# LinTempCont_4ch_proto.net
KiCad netlist of a schematic drawn in EAGLE
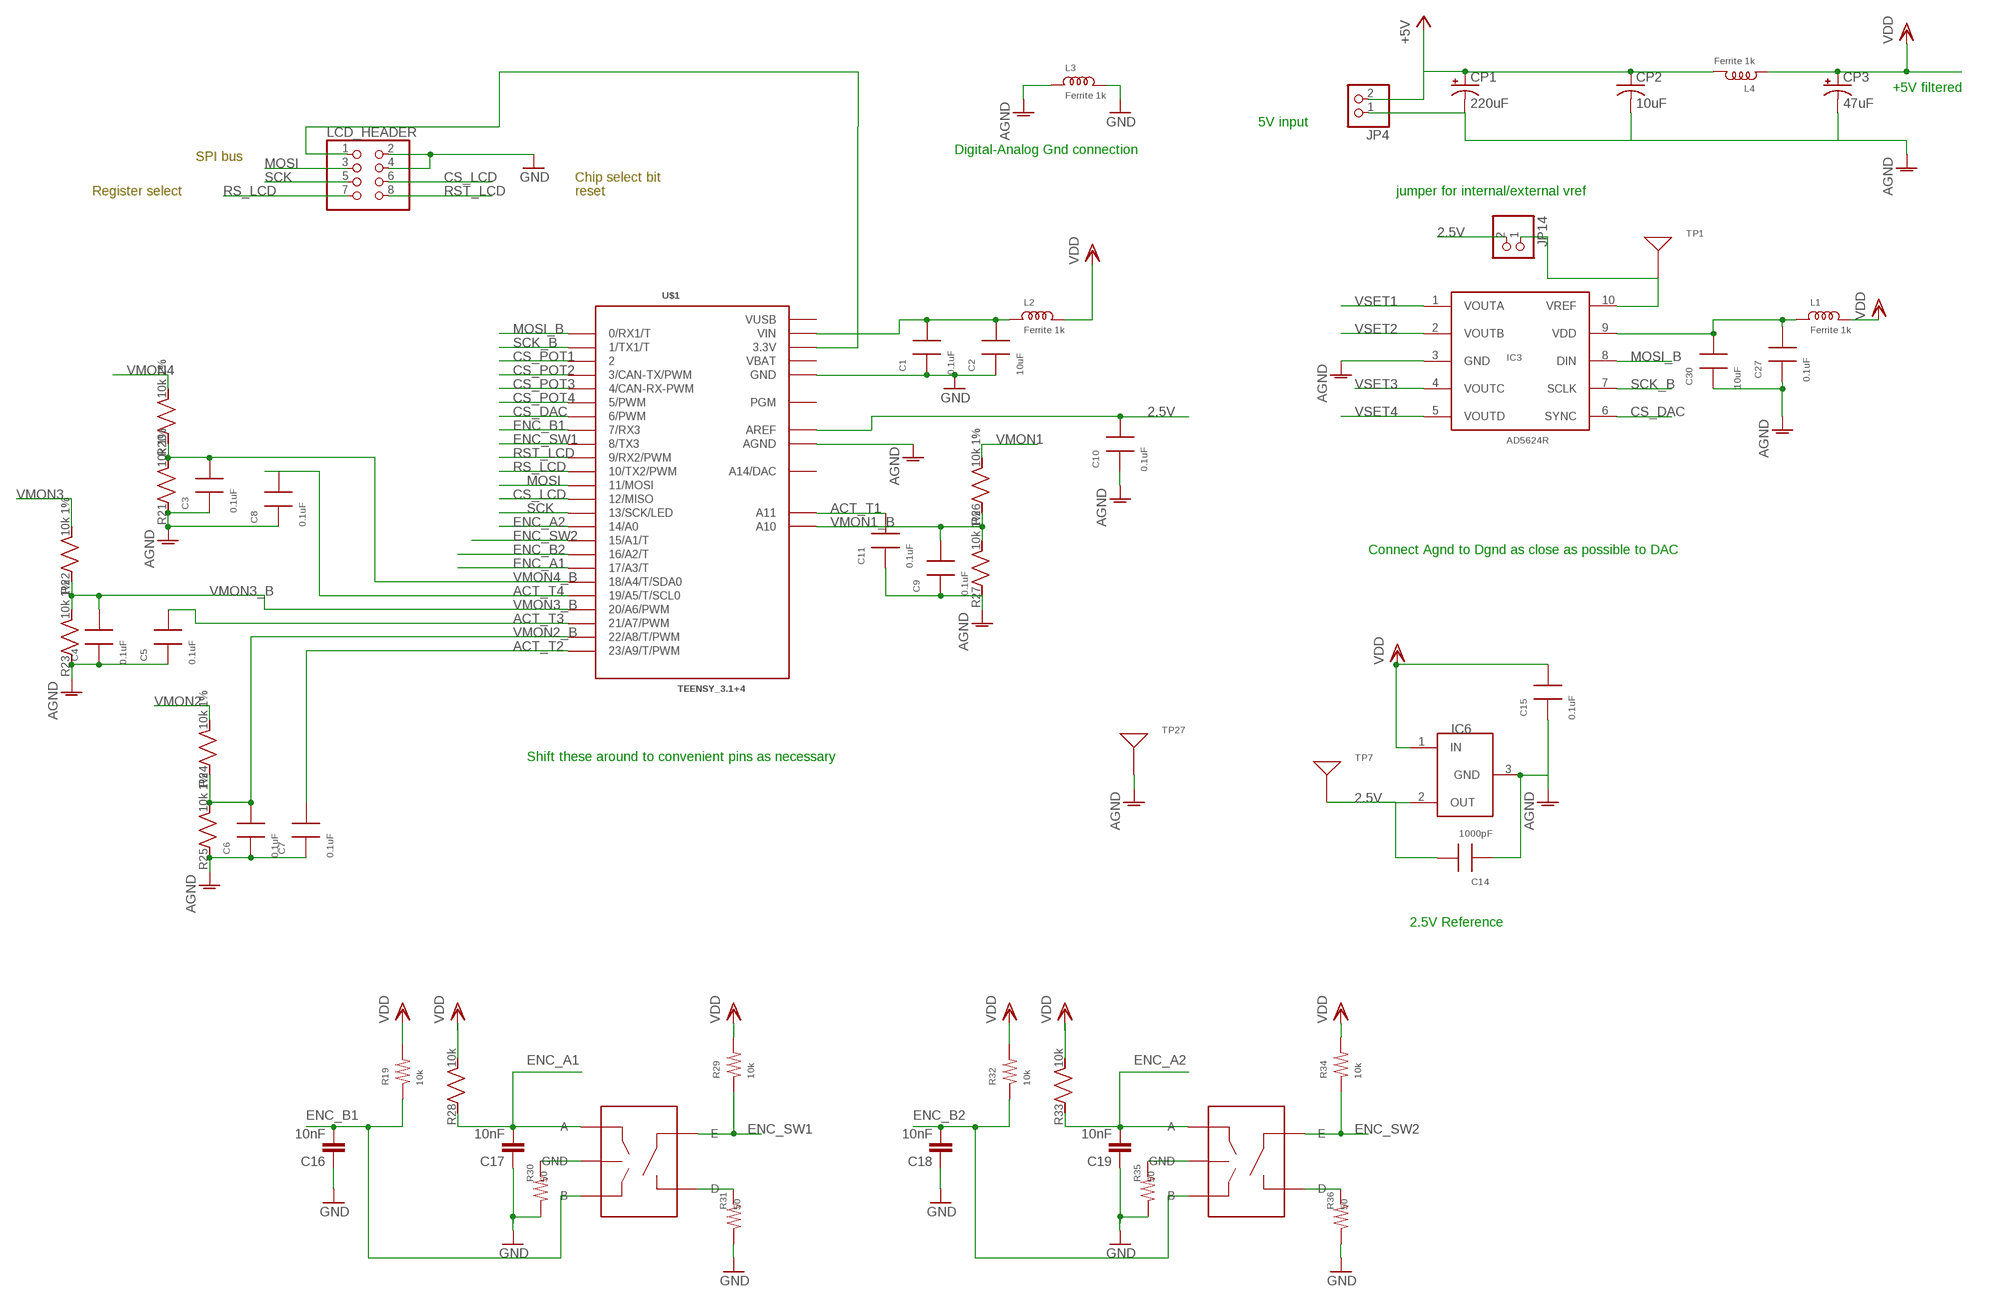
[diagram p0: schematic, sheet 1]
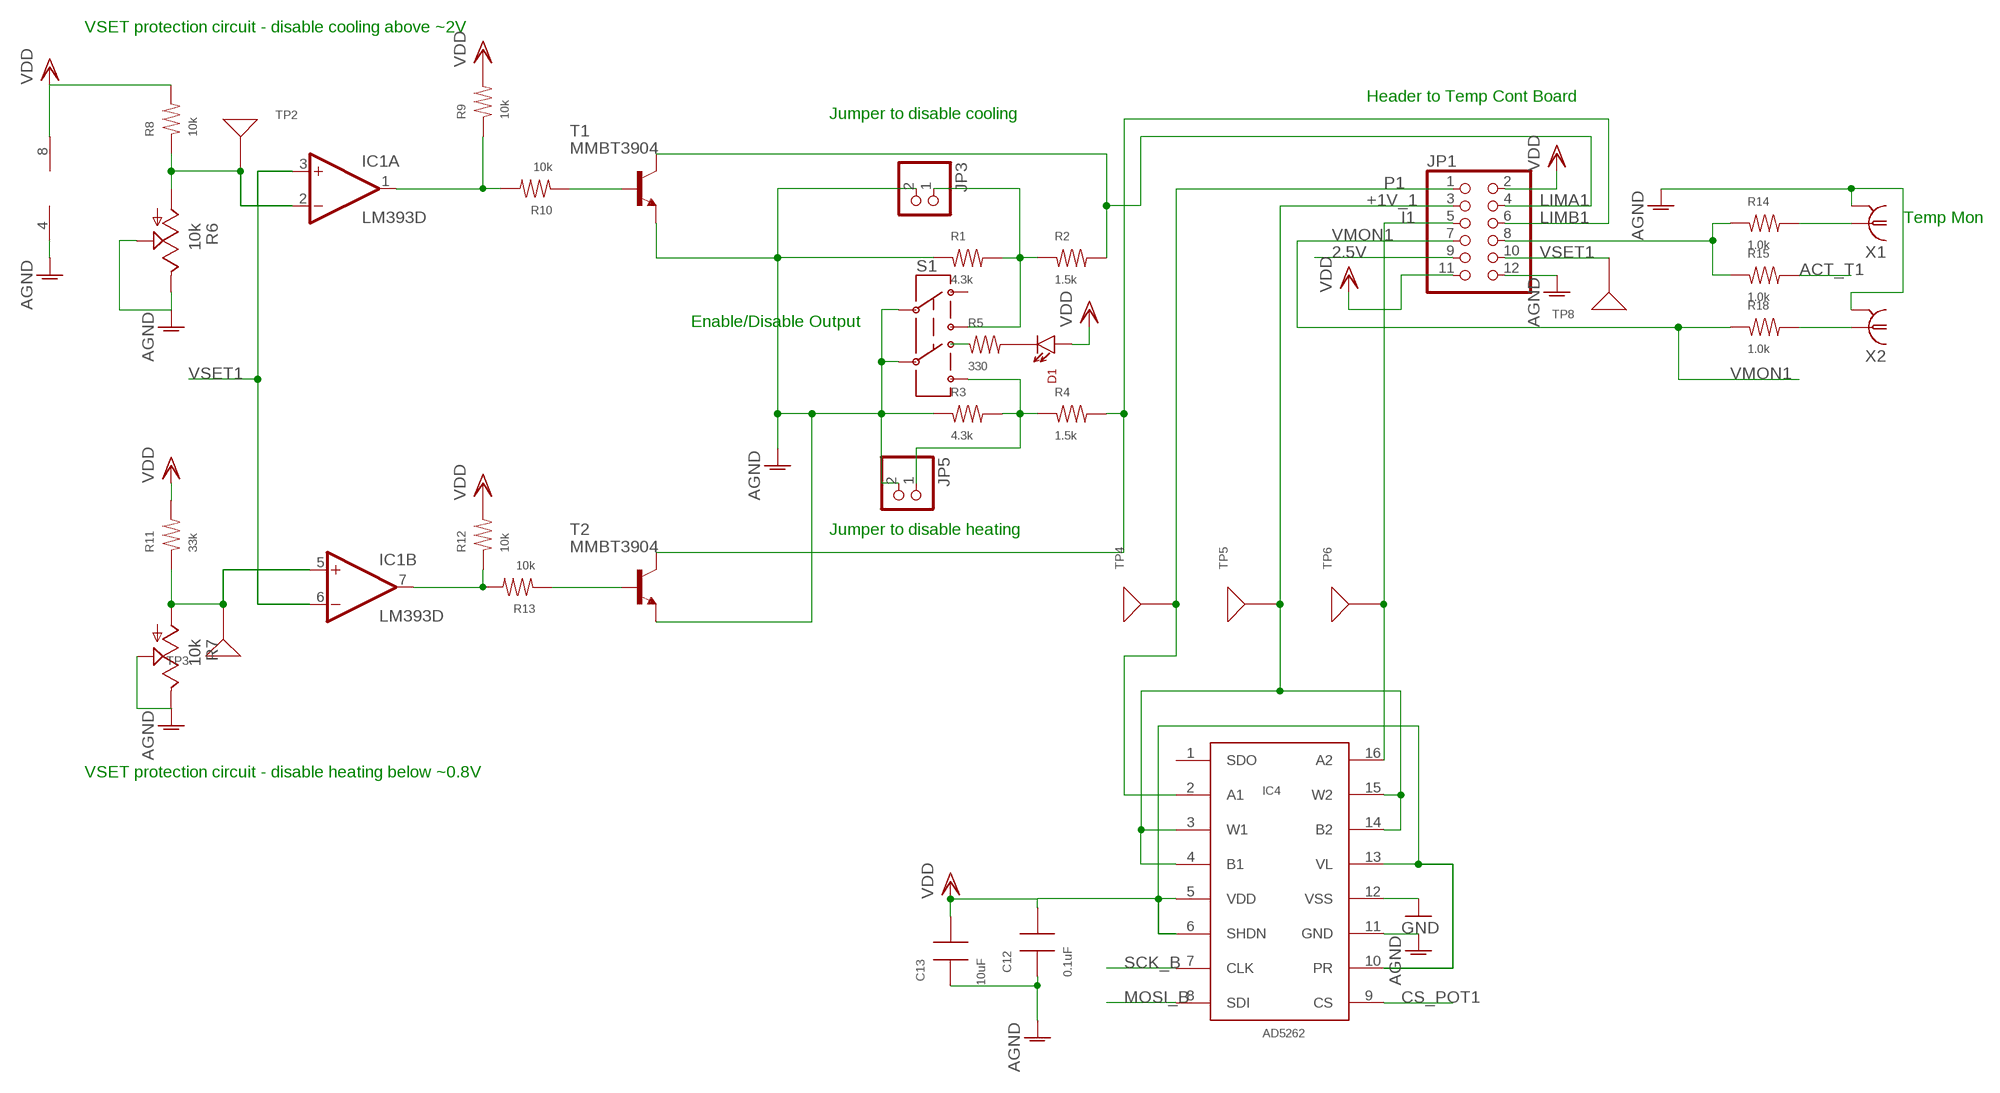
[diagram p1: schematic, sheet 2]
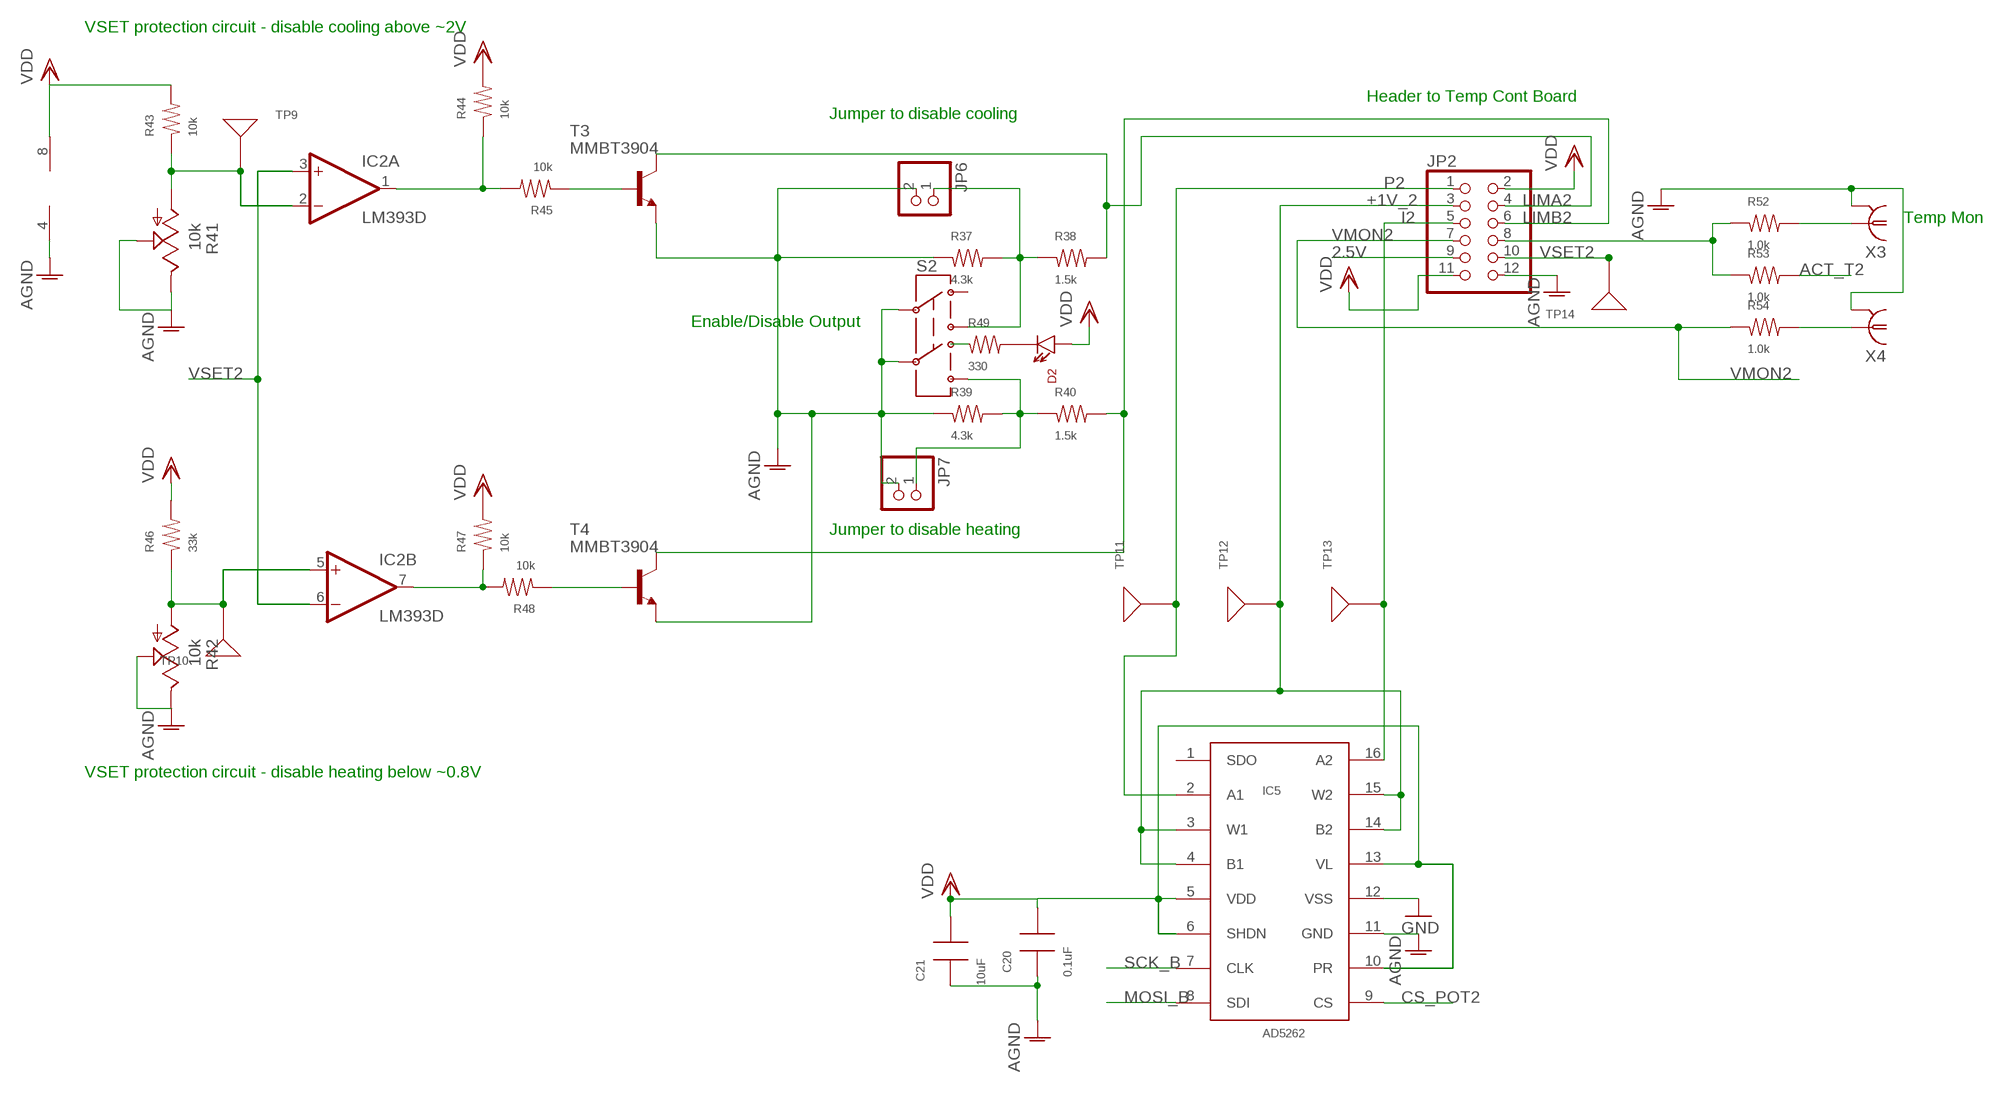
[diagram p2: schematic, sheet 3]
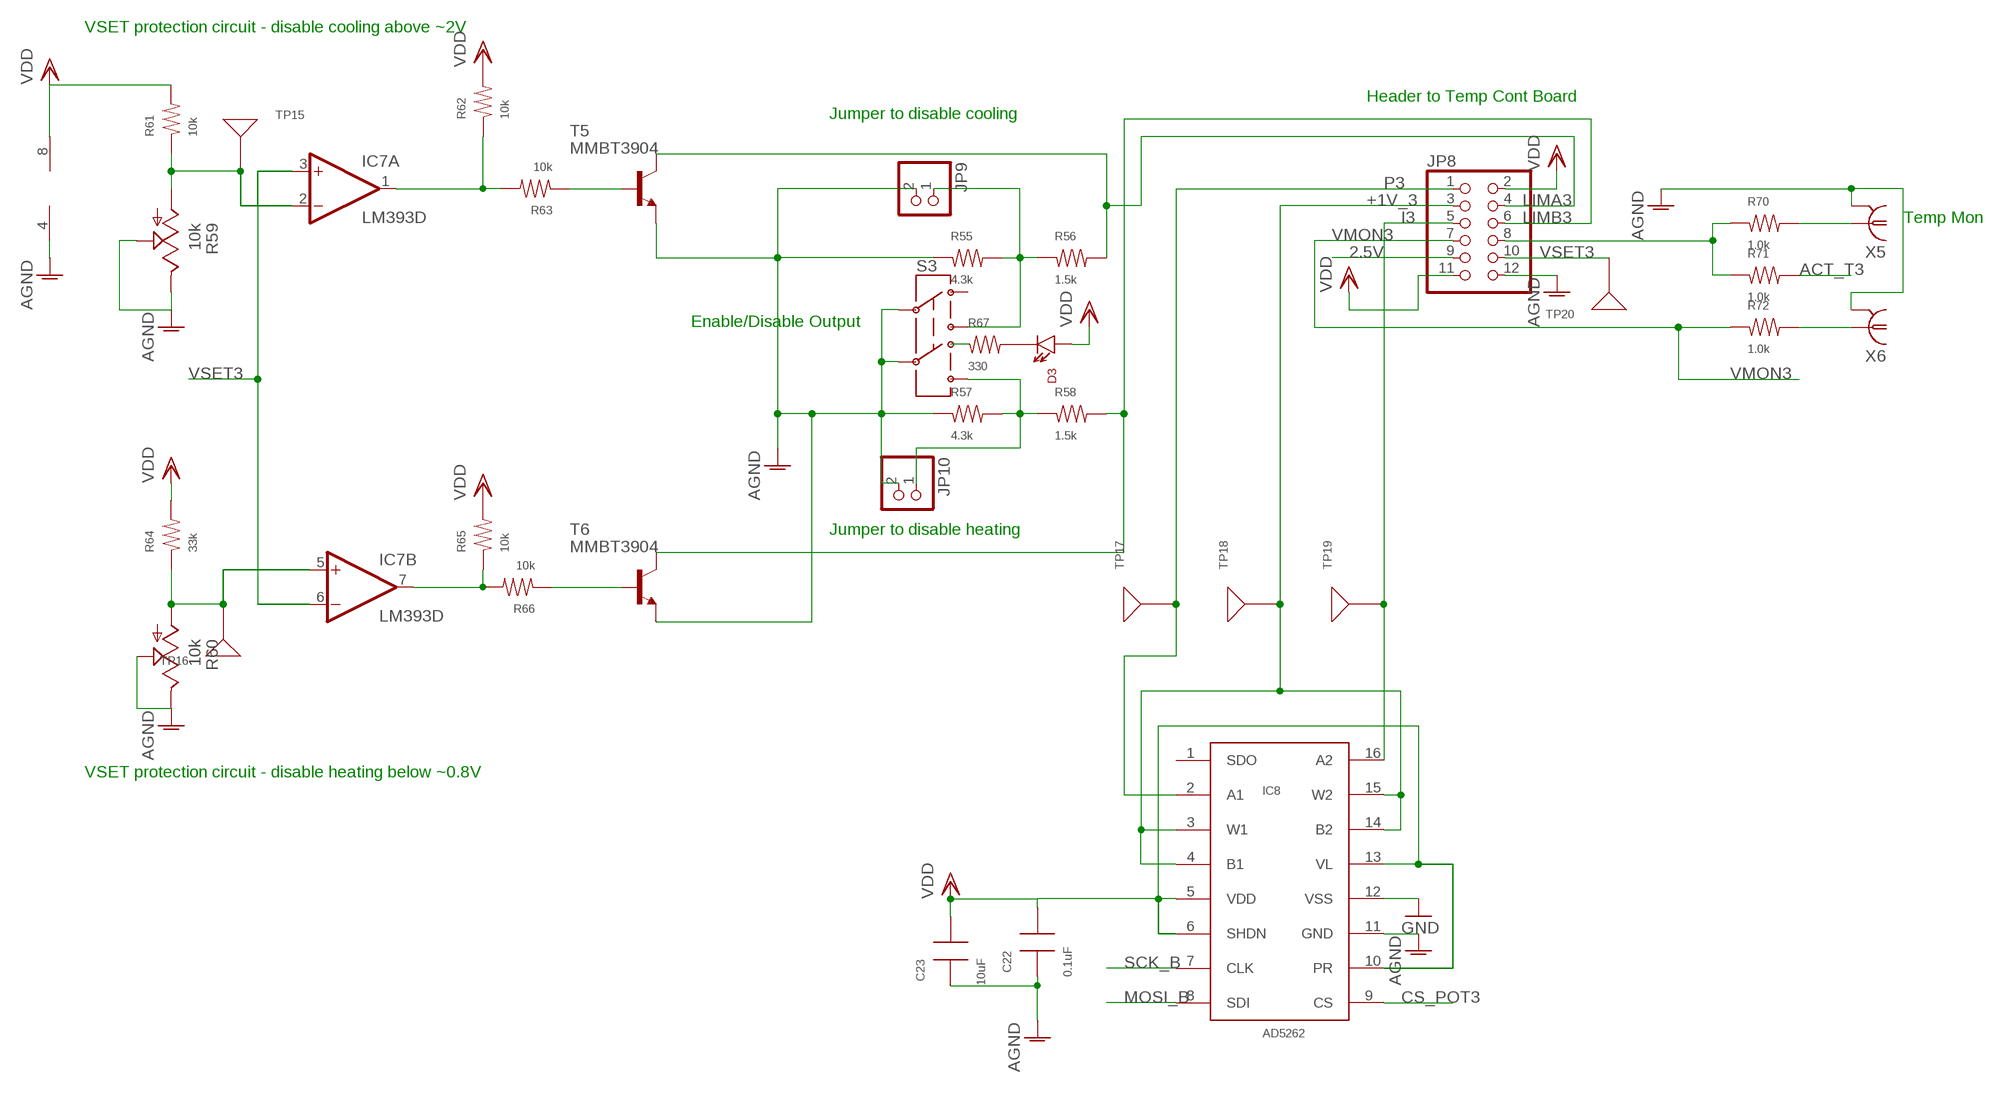
[diagram p3: schematic, sheet 4]
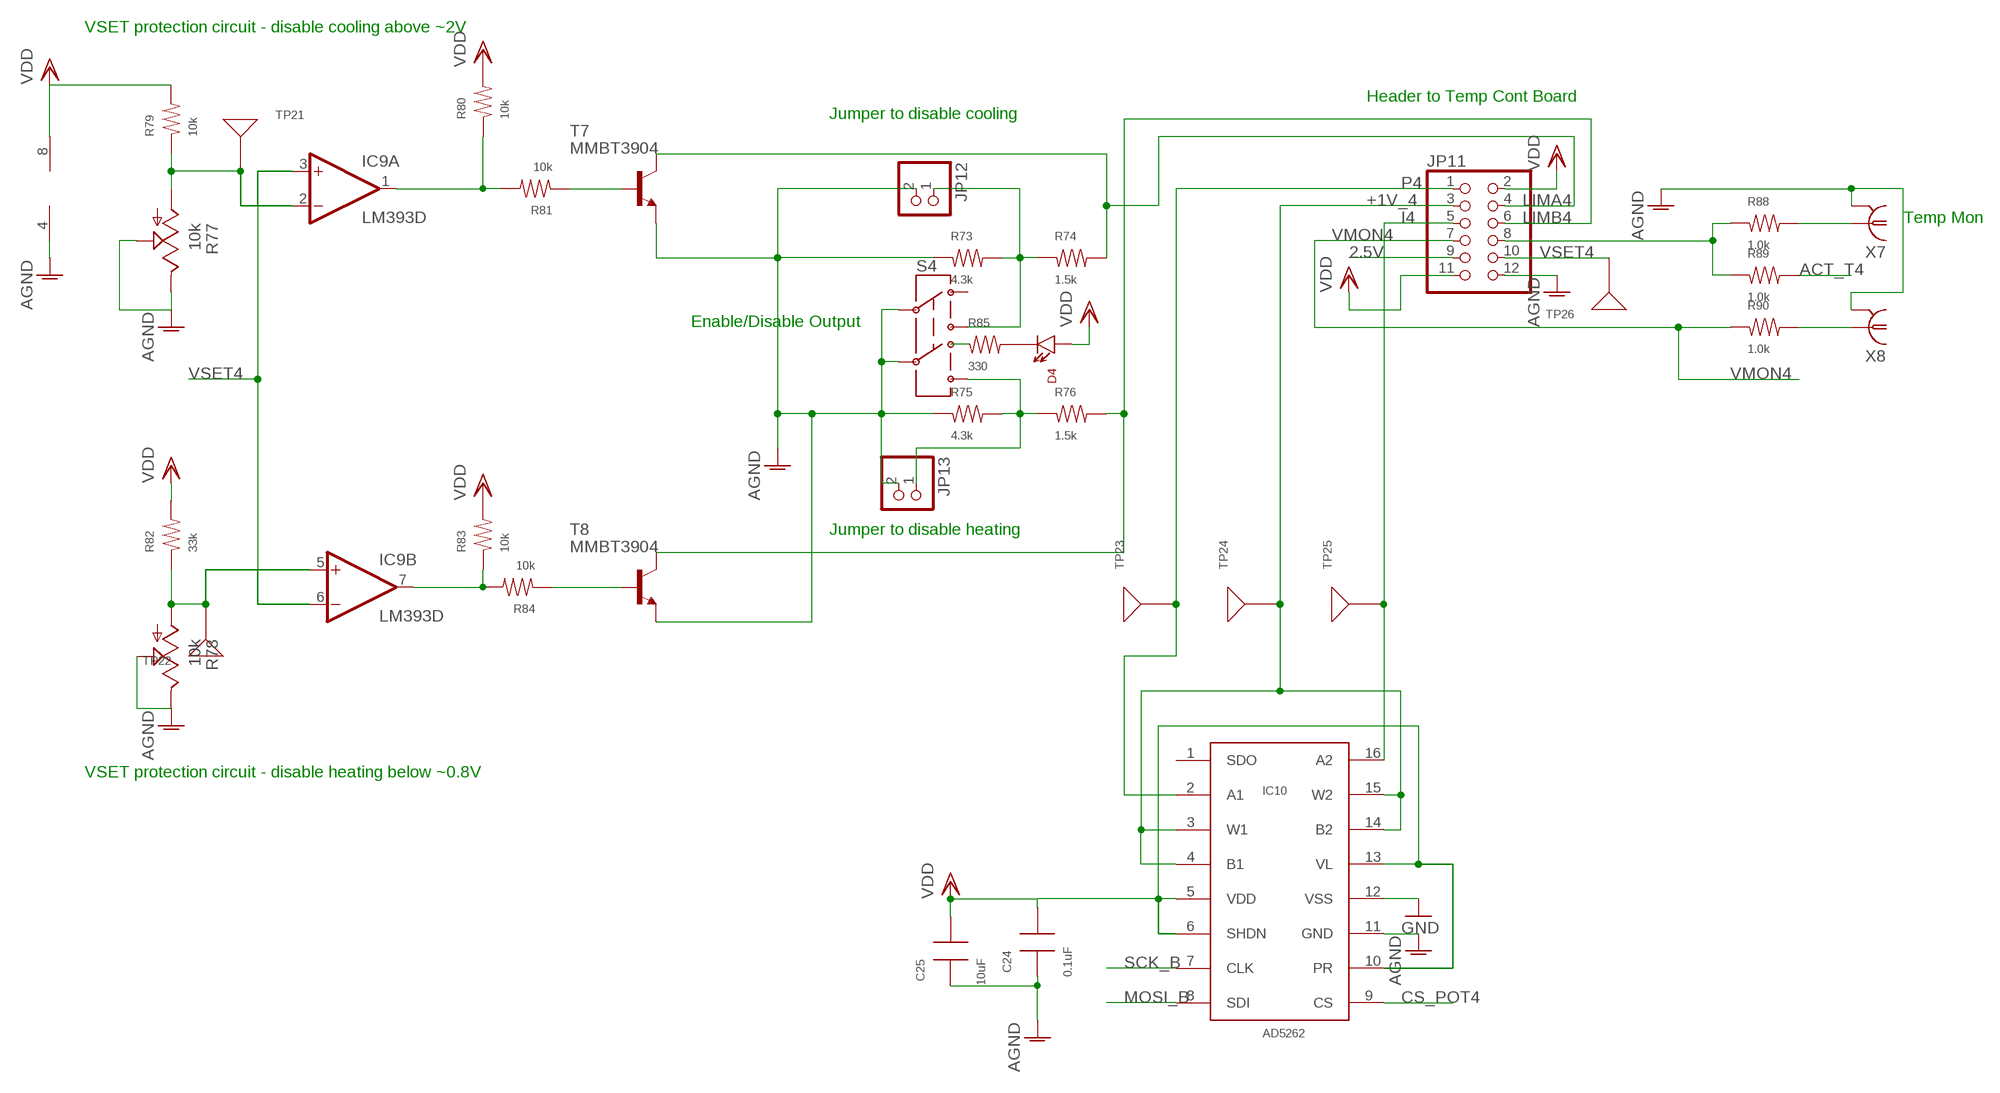
[diagram p4: schematic, sheet 5]

(export (version "E")
  (design (tool "Eeschema 10.0.6"))
  (components
    (comp (ref "C22")
      (value "0.1uF")
      (footprint "eagle-import:0603")
      (libsource (lib "eagle-import") (part "CAP0603"))
    )
    (comp (ref "C23")
      (value "10uF")
      (footprint "eagle-import:0805")
      (libsource (lib "eagle-import") (part "CAP0805"))
    )
    (comp (ref "D3")
      (value "LED/MINI-IND")
      (footprint "eagle-import:HLMP--F0010")
      (libsource (lib "eagle-import") (part "LED/MINI-IND"))
    )
    (comp (ref "IC7")
      (value "LM393D")
      (footprint "eagle-import:SO08")
      (libsource (lib "eagle-import") (part "LM393D"))
    )
    (comp (ref "IC8")
      (value "AD5262")
      (footprint "eagle-import:TSSOP16")
      (libsource (lib "eagle-import") (part "AD5262"))
    )
    (comp (ref "JP8")
      (value "PINHD-2X6/90")
      (footprint "eagle-import:2X06_90")
      (libsource (lib "eagle-import") (part "PINHD-2X6/90"))
    )
    (comp (ref "JP9")
      (value "PINHD-1X2")
      (footprint "eagle-import:1X02")
      (libsource (lib "eagle-import") (part "PINHD-1X2"))
    )
    (comp (ref "JP10")
      (value "PINHD-1X2")
      (footprint "eagle-import:1X02")
      (libsource (lib "eagle-import") (part "PINHD-1X2"))
    )
    (comp (ref "R55")
      (value "4.3k")
      (footprint "eagle-import:0603")
      (libsource (lib "eagle-import") (part "RES0603"))
    )
    (comp (ref "R56")
      (value "1.5k")
      (footprint "eagle-import:0603")
      (libsource (lib "eagle-import") (part "RES0603"))
    )
    (comp (ref "R57")
      (value "4.3k")
      (footprint "eagle-import:0603")
      (libsource (lib "eagle-import") (part "RES0603"))
    )
    (comp (ref "R58")
      (value "1.5k")
      (footprint "eagle-import:0603")
      (libsource (lib "eagle-import") (part "RES0603"))
    )
    (comp (ref "R59")
      (value "10k")
      (footprint "eagle-import:64WPOT")
      (libsource (lib "eagle-import") (part "MODEL64_TRIMPOT/TOP-ADJ"))
    )
    (comp (ref "R60")
      (value "10k")
      (footprint "eagle-import:64WPOT")
      (libsource (lib "eagle-import") (part "MODEL64_TRIMPOT/TOP-ADJ"))
    )
    (comp (ref "R61")
      (value "10k")
      (footprint "eagle-import:0603")
      (libsource (lib "eagle-import") (part "RES0603"))
    )
    (comp (ref "R62")
      (value "10k")
      (footprint "eagle-import:0603")
      (libsource (lib "eagle-import") (part "RES0603"))
    )
    (comp (ref "R63")
      (value "10k")
      (footprint "eagle-import:0603")
      (libsource (lib "eagle-import") (part "RES0603"))
    )
    (comp (ref "R64")
      (value "33k")
      (footprint "eagle-import:0603")
      (libsource (lib "eagle-import") (part "RES0603"))
    )
    (comp (ref "R65")
      (value "10k")
      (footprint "eagle-import:0603")
      (libsource (lib "eagle-import") (part "RES0603"))
    )
    (comp (ref "R66")
      (value "10k")
      (footprint "eagle-import:0603")
      (libsource (lib "eagle-import") (part "RES0603"))
    )
    (comp (ref "R67")
      (value "330")
      (footprint "eagle-import:0603")
      (libsource (lib "eagle-import") (part "RES0603"))
    )
    (comp (ref "R70")
      (value "1.0k")
      (footprint "eagle-import:0603")
      (libsource (lib "eagle-import") (part "RES0603"))
    )
    (comp (ref "R71")
      (value "1.0k")
      (footprint "eagle-import:0603")
      (libsource (lib "eagle-import") (part "RES0603"))
    )
    (comp (ref "R72")
      (value "1.0k")
      (footprint "eagle-import:0603")
      (libsource (lib "eagle-import") (part "RES0603"))
    )
    (comp (ref "S3")
      (value "SWITCH-DPDT/VER")
      (footprint "eagle-import:E-SWITCH-100-M7")
      (libsource (lib "eagle-import") (part "SWITCH-DPDT/VER"))
    )
    (comp (ref "T5")
      (value "MMBT3904")
      (footprint "eagle-import:SOT-23")
      (libsource (lib "eagle-import") (part "MMBT3904"))
    )
    (comp (ref "T6")
      (value "MMBT3904")
      (footprint "eagle-import:SOT-23")
      (libsource (lib "eagle-import") (part "MMBT3904"))
    )
    (comp (ref "TP15")
      (value "TESTPT")
      (footprint "eagle-import:1206TESTPAD")
      (libsource (lib "eagle-import") (part "TESTPT"))
    )
    (comp (ref "TP16")
      (value "TESTPT")
      (footprint "eagle-import:1206TESTPAD")
      (libsource (lib "eagle-import") (part "TESTPT"))
    )
    (comp (ref "TP17")
      (value "TESTPT")
      (footprint "eagle-import:1206TESTPAD")
      (libsource (lib "eagle-import") (part "TESTPT"))
    )
    (comp (ref "TP18")
      (value "TESTPT")
      (footprint "eagle-import:1206TESTPAD")
      (libsource (lib "eagle-import") (part "TESTPT"))
    )
    (comp (ref "TP19")
      (value "TESTPT")
      (footprint "eagle-import:1206TESTPAD")
      (libsource (lib "eagle-import") (part "TESTPT"))
    )
    (comp (ref "TP20")
      (value "TESTPT")
      (footprint "eagle-import:1206TESTPAD")
      (libsource (lib "eagle-import") (part "TESTPT"))
    )
    (comp (ref "X5")
      (value "BNC-H")
      (footprint "eagle-import:BNC90")
      (libsource (lib "eagle-import") (part "BNC-H"))
    )
    (comp (ref "X6")
      (value "BNC-H")
      (footprint "eagle-import:BNC90")
      (libsource (lib "eagle-import") (part "BNC-H"))
    )
    (comp (ref "C24")
      (value "0.1uF")
      (footprint "eagle-import:0603")
      (libsource (lib "eagle-import") (part "CAP0603"))
    )
    (comp (ref "C25")
      (value "10uF")
      (footprint "eagle-import:0805")
      (libsource (lib "eagle-import") (part "CAP0805"))
    )
    (comp (ref "D4")
      (value "LED/MINI-IND")
      (footprint "eagle-import:HLMP--F0010")
      (libsource (lib "eagle-import") (part "LED/MINI-IND"))
    )
    (comp (ref "IC9")
      (value "LM393D")
      (footprint "eagle-import:SO08")
      (libsource (lib "eagle-import") (part "LM393D"))
    )
    (comp (ref "IC10")
      (value "AD5262")
      (footprint "eagle-import:TSSOP16")
      (libsource (lib "eagle-import") (part "AD5262"))
    )
    (comp (ref "JP11")
      (value "PINHD-2X6/90")
      (footprint "eagle-import:2X06_90")
      (libsource (lib "eagle-import") (part "PINHD-2X6/90"))
    )
    (comp (ref "JP12")
      (value "PINHD-1X2")
      (footprint "eagle-import:1X02")
      (libsource (lib "eagle-import") (part "PINHD-1X2"))
    )
    (comp (ref "JP13")
      (value "PINHD-1X2")
      (footprint "eagle-import:1X02")
      (libsource (lib "eagle-import") (part "PINHD-1X2"))
    )
    (comp (ref "R73")
      (value "4.3k")
      (footprint "eagle-import:0603")
      (libsource (lib "eagle-import") (part "RES0603"))
    )
    (comp (ref "R74")
      (value "1.5k")
      (footprint "eagle-import:0603")
      (libsource (lib "eagle-import") (part "RES0603"))
    )
    (comp (ref "R75")
      (value "4.3k")
      (footprint "eagle-import:0603")
      (libsource (lib "eagle-import") (part "RES0603"))
    )
    (comp (ref "R76")
      (value "1.5k")
      (footprint "eagle-import:0603")
      (libsource (lib "eagle-import") (part "RES0603"))
    )
    (comp (ref "R77")
      (value "10k")
      (footprint "eagle-import:64WPOT")
      (libsource (lib "eagle-import") (part "MODEL64_TRIMPOT/TOP-ADJ"))
    )
    (comp (ref "R78")
      (value "10k")
      (footprint "eagle-import:64WPOT")
      (libsource (lib "eagle-import") (part "MODEL64_TRIMPOT/TOP-ADJ"))
    )
    (comp (ref "R79")
      (value "10k")
      (footprint "eagle-import:0603")
      (libsource (lib "eagle-import") (part "RES0603"))
    )
    (comp (ref "R80")
      (value "10k")
      (footprint "eagle-import:0603")
      (libsource (lib "eagle-import") (part "RES0603"))
    )
    (comp (ref "R81")
      (value "10k")
      (footprint "eagle-import:0603")
      (libsource (lib "eagle-import") (part "RES0603"))
    )
    (comp (ref "R82")
      (value "33k")
      (footprint "eagle-import:0603")
      (libsource (lib "eagle-import") (part "RES0603"))
    )
    (comp (ref "R83")
      (value "10k")
      (footprint "eagle-import:0603")
      (libsource (lib "eagle-import") (part "RES0603"))
    )
    (comp (ref "R84")
      (value "10k")
      (footprint "eagle-import:0603")
      (libsource (lib "eagle-import") (part "RES0603"))
    )
    (comp (ref "R85")
      (value "330")
      (footprint "eagle-import:0603")
      (libsource (lib "eagle-import") (part "RES0603"))
    )
    (comp (ref "R88")
      (value "1.0k")
      (footprint "eagle-import:0603")
      (libsource (lib "eagle-import") (part "RES0603"))
    )
    (comp (ref "R89")
      (value "1.0k")
      (footprint "eagle-import:0603")
      (libsource (lib "eagle-import") (part "RES0603"))
    )
    (comp (ref "R90")
      (value "1.0k")
      (footprint "eagle-import:0603")
      (libsource (lib "eagle-import") (part "RES0603"))
    )
    (comp (ref "S4")
      (value "SWITCH-DPDT/VER")
      (footprint "eagle-import:E-SWITCH-100-M7")
      (libsource (lib "eagle-import") (part "SWITCH-DPDT/VER"))
    )
    (comp (ref "T7")
      (value "MMBT3904")
      (footprint "eagle-import:SOT-23")
      (libsource (lib "eagle-import") (part "MMBT3904"))
    )
    (comp (ref "T8")
      (value "MMBT3904")
      (footprint "eagle-import:SOT-23")
      (libsource (lib "eagle-import") (part "MMBT3904"))
    )
    (comp (ref "TP21")
      (value "TESTPT")
      (footprint "eagle-import:1206TESTPAD")
      (libsource (lib "eagle-import") (part "TESTPT"))
    )
    (comp (ref "TP22")
      (value "TESTPT")
      (footprint "eagle-import:1206TESTPAD")
      (libsource (lib "eagle-import") (part "TESTPT"))
    )
    (comp (ref "TP23")
      (value "TESTPT")
      (footprint "eagle-import:1206TESTPAD")
      (libsource (lib "eagle-import") (part "TESTPT"))
    )
    (comp (ref "TP24")
      (value "TESTPT")
      (footprint "eagle-import:1206TESTPAD")
      (libsource (lib "eagle-import") (part "TESTPT"))
    )
    (comp (ref "TP25")
      (value "TESTPT")
      (footprint "eagle-import:1206TESTPAD")
      (libsource (lib "eagle-import") (part "TESTPT"))
    )
    (comp (ref "TP26")
      (value "TESTPT")
      (footprint "eagle-import:1206TESTPAD")
      (libsource (lib "eagle-import") (part "TESTPT"))
    )
    (comp (ref "X7")
      (value "BNC-H")
      (footprint "eagle-import:BNC90")
      (libsource (lib "eagle-import") (part "BNC-H"))
    )
    (comp (ref "X8")
      (value "BNC-H")
      (footprint "eagle-import:BNC90")
      (libsource (lib "eagle-import") (part "BNC-H"))
    )
    (comp (ref "C1")
      (value "0.1uF")
      (footprint "eagle-import:0603")
      (libsource (lib "eagle-import") (part "CAP0603"))
    )
    (comp (ref "C2")
      (value "10uF")
      (footprint "eagle-import:0805")
      (libsource (lib "eagle-import") (part "CAP0805"))
    )
    (comp (ref "C3")
      (value "0.1uF")
      (footprint "eagle-import:0603")
      (libsource (lib "eagle-import") (part "CAP0603"))
    )
    (comp (ref "C4")
      (value "0.1uF")
      (footprint "eagle-import:0603")
      (libsource (lib "eagle-import") (part "CAP0603"))
    )
    (comp (ref "C5")
      (value "0.1uF")
      (footprint "eagle-import:0603")
      (libsource (lib "eagle-import") (part "CAP0603"))
    )
    (comp (ref "C6")
      (value "0.1uF")
      (footprint "eagle-import:0603")
      (libsource (lib "eagle-import") (part "CAP0603"))
    )
    (comp (ref "C7")
      (value "0.1uF")
      (footprint "eagle-import:0603")
      (libsource (lib "eagle-import") (part "CAP0603"))
    )
    (comp (ref "C8")
      (value "0.1uF")
      (footprint "eagle-import:0603")
      (libsource (lib "eagle-import") (part "CAP0603"))
    )
    (comp (ref "C9")
      (value "0.1uF")
      (footprint "eagle-import:0603")
      (libsource (lib "eagle-import") (part "CAP0603"))
    )
    (comp (ref "C10")
      (value "0.1uF")
      (footprint "eagle-import:0603")
      (libsource (lib "eagle-import") (part "CAP0603"))
    )
    (comp (ref "C11")
      (value "0.1uF")
      (footprint "eagle-import:0603")
      (libsource (lib "eagle-import") (part "CAP0603"))
    )
    (comp (ref "C14")
      (value "1000pF")
      (footprint "eagle-import:0603")
      (libsource (lib "eagle-import") (part "CAP0603"))
    )
    (comp (ref "C15")
      (value "0.1uF")
      (footprint "eagle-import:0603")
      (libsource (lib "eagle-import") (part "CAP0603"))
    )
    (comp (ref "C16")
      (value "10nF")
      (footprint "eagle-import:C0603")
      (libsource (lib "eagle-import") (part "C-EUC0603"))
    )
    (comp (ref "C17")
      (value "10nF")
      (footprint "eagle-import:C0603")
      (libsource (lib "eagle-import") (part "C-EUC0603"))
    )
    (comp (ref "C18")
      (value "10nF")
      (footprint "eagle-import:C0603")
      (libsource (lib "eagle-import") (part "C-EUC0603"))
    )
    (comp (ref "C19")
      (value "10nF")
      (footprint "eagle-import:C0603")
      (libsource (lib "eagle-import") (part "C-EUC0603"))
    )
    (comp (ref "C27")
      (value "0.1uF")
      (footprint "eagle-import:0603")
      (libsource (lib "eagle-import") (part "CAP0603"))
    )
    (comp (ref "C30")
      (value "10uF")
      (footprint "eagle-import:0805")
      (libsource (lib "eagle-import") (part "CAP0805"))
    )
    (comp (ref "CP1")
      (value "220uF")
      (footprint "eagle-import:PANASONIC_F")
      (libsource (lib "eagle-import") (part "CPOL-USF"))
    )
    (comp (ref "CP2")
      (value "10uF")
      (footprint "eagle-import:C0805K")
      (libsource (lib "eagle-import") (part "C-USC0805K"))
    )
    (comp (ref "CP3")
      (value "47uF")
      (footprint "eagle-import:CT7343")
      (libsource (lib "eagle-import") (part "CPOL-USCT7343"))
    )
    (comp (ref "ENC1")
      (value "PEC09")
      (footprint "eagle-import:PEC092320FS")
      (libsource (lib "eagle-import") (part "PEC09"))
    )
    (comp (ref "ENC2")
      (value "PEC09")
      (footprint "eagle-import:PEC092320FS")
      (libsource (lib "eagle-import") (part "PEC09"))
    )
    (comp (ref "IC3")
      (value "AD5624R")
      (footprint "eagle-import:MSOP10")
      (libsource (lib "eagle-import") (part "AD5624R"))
    )
    (comp (ref "IC6")
      (value "TS6001")
      (footprint "eagle-import:SOT-23")
      (libsource (lib "eagle-import") (part "TS6001"))
    )
    (comp (ref "JP4")
      (value "SCRWTRM-1X2")
      (footprint "eagle-import:1X02_SCRWTRM")
      (libsource (lib "eagle-import") (part "SCRWTRM-1X2"))
    )
    (comp (ref "JP14")
      (value "PINHD-1X2")
      (footprint "eagle-import:1X02")
      (libsource (lib "eagle-import") (part "PINHD-1X2"))
    )
    (comp (ref "L1")
      (value "Ferrite 1k")
      (footprint "eagle-import:0805")
      (libsource (lib "eagle-import") (part "INDUCTOR-0805"))
    )
    (comp (ref "L2")
      (value "Ferrite 1k")
      (footprint "eagle-import:0805")
      (libsource (lib "eagle-import") (part "INDUCTOR-0805"))
    )
    (comp (ref "L3")
      (value "Ferrite 1k")
      (footprint "eagle-import:0805")
      (libsource (lib "eagle-import") (part "INDUCTOR-0805"))
    )
    (comp (ref "L4")
      (value "Ferrite 1k")
      (footprint "eagle-import:0805")
      (libsource (lib "eagle-import") (part "INDUCTOR-0805"))
    )
    (comp (ref "LCD_HEADER")
      (value "PINHD-2X4-SHROUD")
      (footprint "eagle-import:ML08")
      (libsource (lib "eagle-import") (part "PINHD-2X4-SHROUD"))
    )
    (comp (ref "R19")
      (value "10k")
      (footprint "eagle-import:0603")
      (libsource (lib "eagle-import") (part "RES0603"))
    )
    (comp (ref "R20")
      (value "10k 1%")
      (footprint "eagle-import:R_0603")
      (libsource (lib "eagle-import") (part "R_SMDR0603"))
    )
    (comp (ref "R21")
      (value "10k 1%")
      (footprint "eagle-import:R_0603")
      (libsource (lib "eagle-import") (part "R_SMDR0603"))
    )
    (comp (ref "R22")
      (value "10k 1%")
      (footprint "eagle-import:R_0603")
      (libsource (lib "eagle-import") (part "R_SMDR0603"))
    )
    (comp (ref "R23")
      (value "10k 1%")
      (footprint "eagle-import:R_0603")
      (libsource (lib "eagle-import") (part "R_SMDR0603"))
    )
    (comp (ref "R24")
      (value "10k 1%")
      (footprint "eagle-import:R_0603")
      (libsource (lib "eagle-import") (part "R_SMDR0603"))
    )
    (comp (ref "R25")
      (value "10k 1%")
      (footprint "eagle-import:R_0603")
      (libsource (lib "eagle-import") (part "R_SMDR0603"))
    )
    (comp (ref "R26")
      (value "10k 1%")
      (footprint "eagle-import:R_0603")
      (libsource (lib "eagle-import") (part "R_SMDR0603"))
    )
    (comp (ref "R27")
      (value "10k 1%")
      (footprint "eagle-import:R_0603")
      (libsource (lib "eagle-import") (part "R_SMDR0603"))
    )
    (comp (ref "R28")
      (value "10k")
      (footprint "eagle-import:R_0603")
      (libsource (lib "eagle-import") (part "R_SMDR0603"))
    )
    (comp (ref "R29")
      (value "10k")
      (footprint "eagle-import:0603")
      (libsource (lib "eagle-import") (part "RES0603"))
    )
    (comp (ref "R30")
      (value "50")
      (footprint "eagle-import:0603")
      (libsource (lib "eagle-import") (part "RES0603"))
    )
    (comp (ref "R31")
      (value "50")
      (footprint "eagle-import:0603")
      (libsource (lib "eagle-import") (part "RES0603"))
    )
    (comp (ref "R32")
      (value "10k")
      (footprint "eagle-import:0603")
      (libsource (lib "eagle-import") (part "RES0603"))
    )
    (comp (ref "R33")
      (value "10k")
      (footprint "eagle-import:R_0603")
      (libsource (lib "eagle-import") (part "R_SMDR0603"))
    )
    (comp (ref "R34")
      (value "10k")
      (footprint "eagle-import:0603")
      (libsource (lib "eagle-import") (part "RES0603"))
    )
    (comp (ref "R35")
      (value "50")
      (footprint "eagle-import:0603")
      (libsource (lib "eagle-import") (part "RES0603"))
    )
    (comp (ref "R36")
      (value "50")
      (footprint "eagle-import:0603")
      (libsource (lib "eagle-import") (part "RES0603"))
    )
    (comp (ref "TP1")
      (value "TESTPT")
      (footprint "eagle-import:1206TESTPAD")
      (libsource (lib "eagle-import") (part "TESTPT"))
    )
    (comp (ref "TP7")
      (value "TESTPT")
      (footprint "eagle-import:1206TESTPAD")
      (libsource (lib "eagle-import") (part "TESTPT"))
    )
    (comp (ref "TP27")
      (value "TESTPT")
      (footprint "eagle-import:1206TESTPAD")
      (libsource (lib "eagle-import") (part "TESTPT"))
    )
    (comp (ref "U$1")
      (value "TEENSY_3.1+4")
      (footprint "eagle-import:TEENSY_3.1+4")
      (libsource (lib "eagle-import") (part "TEENSY_3.1+4"))
    )
    (comp (ref "C12")
      (value "0.1uF")
      (footprint "eagle-import:0603")
      (libsource (lib "eagle-import") (part "CAP0603"))
    )
    (comp (ref "C13")
      (value "10uF")
      (footprint "eagle-import:0805")
      (libsource (lib "eagle-import") (part "CAP0805"))
    )
    (comp (ref "D1")
      (value "LED/MINI-IND")
      (footprint "eagle-import:HLMP--F0010")
      (libsource (lib "eagle-import") (part "LED/MINI-IND"))
    )
    (comp (ref "IC1")
      (value "LM393D")
      (footprint "eagle-import:SO08")
      (libsource (lib "eagle-import") (part "LM393D"))
    )
    (comp (ref "IC4")
      (value "AD5262")
      (footprint "eagle-import:TSSOP16")
      (libsource (lib "eagle-import") (part "AD5262"))
    )
    (comp (ref "JP1")
      (value "PINHD-2X6/90")
      (footprint "eagle-import:2X06_90")
      (libsource (lib "eagle-import") (part "PINHD-2X6/90"))
    )
    (comp (ref "JP3")
      (value "PINHD-1X2")
      (footprint "eagle-import:1X02")
      (libsource (lib "eagle-import") (part "PINHD-1X2"))
    )
    (comp (ref "JP5")
      (value "PINHD-1X2")
      (footprint "eagle-import:1X02")
      (libsource (lib "eagle-import") (part "PINHD-1X2"))
    )
    (comp (ref "R1")
      (value "4.3k")
      (footprint "eagle-import:0603")
      (libsource (lib "eagle-import") (part "RES0603"))
    )
    (comp (ref "R2")
      (value "1.5k")
      (footprint "eagle-import:0603")
      (libsource (lib "eagle-import") (part "RES0603"))
    )
    (comp (ref "R3")
      (value "4.3k")
      (footprint "eagle-import:0603")
      (libsource (lib "eagle-import") (part "RES0603"))
    )
    (comp (ref "R4")
      (value "1.5k")
      (footprint "eagle-import:0603")
      (libsource (lib "eagle-import") (part "RES0603"))
    )
    (comp (ref "R5")
      (value "330")
      (footprint "eagle-import:0603")
      (libsource (lib "eagle-import") (part "RES0603"))
    )
    (comp (ref "R6")
      (value "10k")
      (footprint "eagle-import:64WPOT")
      (libsource (lib "eagle-import") (part "MODEL64_TRIMPOT/TOP-ADJ"))
    )
    (comp (ref "R7")
      (value "10k")
      (footprint "eagle-import:64WPOT")
      (libsource (lib "eagle-import") (part "MODEL64_TRIMPOT/TOP-ADJ"))
    )
    (comp (ref "R8")
      (value "10k")
      (footprint "eagle-import:0603")
      (libsource (lib "eagle-import") (part "RES0603"))
    )
    (comp (ref "R9")
      (value "10k")
      (footprint "eagle-import:0603")
      (libsource (lib "eagle-import") (part "RES0603"))
    )
    (comp (ref "R10")
      (value "10k")
      (footprint "eagle-import:0603")
      (libsource (lib "eagle-import") (part "RES0603"))
    )
    (comp (ref "R11")
      (value "33k")
      (footprint "eagle-import:0603")
      (libsource (lib "eagle-import") (part "RES0603"))
    )
    (comp (ref "R12")
      (value "10k")
      (footprint "eagle-import:0603")
      (libsource (lib "eagle-import") (part "RES0603"))
    )
    (comp (ref "R13")
      (value "10k")
      (footprint "eagle-import:0603")
      (libsource (lib "eagle-import") (part "RES0603"))
    )
    (comp (ref "R14")
      (value "1.0k")
      (footprint "eagle-import:0603")
      (libsource (lib "eagle-import") (part "RES0603"))
    )
    (comp (ref "R15")
      (value "1.0k")
      (footprint "eagle-import:0603")
      (libsource (lib "eagle-import") (part "RES0603"))
    )
    (comp (ref "R18")
      (value "1.0k")
      (footprint "eagle-import:0603")
      (libsource (lib "eagle-import") (part "RES0603"))
    )
    (comp (ref "S1")
      (value "SWITCH-DPDT/VER")
      (footprint "eagle-import:E-SWITCH-100-M7")
      (libsource (lib "eagle-import") (part "SWITCH-DPDT/VER"))
    )
    (comp (ref "T1")
      (value "MMBT3904")
      (footprint "eagle-import:SOT-23")
      (libsource (lib "eagle-import") (part "MMBT3904"))
    )
    (comp (ref "T2")
      (value "MMBT3904")
      (footprint "eagle-import:SOT-23")
      (libsource (lib "eagle-import") (part "MMBT3904"))
    )
    (comp (ref "TP2")
      (value "TESTPT")
      (footprint "eagle-import:1206TESTPAD")
      (libsource (lib "eagle-import") (part "TESTPT"))
    )
    (comp (ref "TP3")
      (value "TESTPT")
      (footprint "eagle-import:1206TESTPAD")
      (libsource (lib "eagle-import") (part "TESTPT"))
    )
    (comp (ref "TP4")
      (value "TESTPT")
      (footprint "eagle-import:1206TESTPAD")
      (libsource (lib "eagle-import") (part "TESTPT"))
    )
    (comp (ref "TP5")
      (value "TESTPT")
      (footprint "eagle-import:1206TESTPAD")
      (libsource (lib "eagle-import") (part "TESTPT"))
    )
    (comp (ref "TP6")
      (value "TESTPT")
      (footprint "eagle-import:1206TESTPAD")
      (libsource (lib "eagle-import") (part "TESTPT"))
    )
    (comp (ref "TP8")
      (value "TESTPT")
      (footprint "eagle-import:1206TESTPAD")
      (libsource (lib "eagle-import") (part "TESTPT"))
    )
    (comp (ref "X1")
      (value "BNC-H")
      (footprint "eagle-import:BNC90")
      (libsource (lib "eagle-import") (part "BNC-H"))
    )
    (comp (ref "X2")
      (value "BNC-H")
      (footprint "eagle-import:BNC90")
      (libsource (lib "eagle-import") (part "BNC-H"))
    )
    (comp (ref "C20")
      (value "0.1uF")
      (footprint "eagle-import:0603")
      (libsource (lib "eagle-import") (part "CAP0603"))
    )
    (comp (ref "C21")
      (value "10uF")
      (footprint "eagle-import:0805")
      (libsource (lib "eagle-import") (part "CAP0805"))
    )
    (comp (ref "D2")
      (value "LED/MINI-IND")
      (footprint "eagle-import:HLMP--F0010")
      (libsource (lib "eagle-import") (part "LED/MINI-IND"))
    )
    (comp (ref "IC2")
      (value "LM393D")
      (footprint "eagle-import:SO08")
      (libsource (lib "eagle-import") (part "LM393D"))
    )
    (comp (ref "IC5")
      (value "AD5262")
      (footprint "eagle-import:TSSOP16")
      (libsource (lib "eagle-import") (part "AD5262"))
    )
    (comp (ref "JP2")
      (value "PINHD-2X6/90")
      (footprint "eagle-import:2X06_90")
      (libsource (lib "eagle-import") (part "PINHD-2X6/90"))
    )
    (comp (ref "JP6")
      (value "PINHD-1X2")
      (footprint "eagle-import:1X02")
      (libsource (lib "eagle-import") (part "PINHD-1X2"))
    )
    (comp (ref "JP7")
      (value "PINHD-1X2")
      (footprint "eagle-import:1X02")
      (libsource (lib "eagle-import") (part "PINHD-1X2"))
    )
    (comp (ref "R37")
      (value "4.3k")
      (footprint "eagle-import:0603")
      (libsource (lib "eagle-import") (part "RES0603"))
    )
    (comp (ref "R38")
      (value "1.5k")
      (footprint "eagle-import:0603")
      (libsource (lib "eagle-import") (part "RES0603"))
    )
    (comp (ref "R39")
      (value "4.3k")
      (footprint "eagle-import:0603")
      (libsource (lib "eagle-import") (part "RES0603"))
    )
    (comp (ref "R40")
      (value "1.5k")
      (footprint "eagle-import:0603")
      (libsource (lib "eagle-import") (part "RES0603"))
    )
    (comp (ref "R41")
      (value "10k")
      (footprint "eagle-import:64WPOT")
      (libsource (lib "eagle-import") (part "MODEL64_TRIMPOT/TOP-ADJ"))
    )
    (comp (ref "R42")
      (value "10k")
      (footprint "eagle-import:64WPOT")
      (libsource (lib "eagle-import") (part "MODEL64_TRIMPOT/TOP-ADJ"))
    )
    (comp (ref "R43")
      (value "10k")
      (footprint "eagle-import:0603")
      (libsource (lib "eagle-import") (part "RES0603"))
    )
    (comp (ref "R44")
      (value "10k")
      (footprint "eagle-import:0603")
      (libsource (lib "eagle-import") (part "RES0603"))
    )
    (comp (ref "R45")
      (value "10k")
      (footprint "eagle-import:0603")
      (libsource (lib "eagle-import") (part "RES0603"))
    )
    (comp (ref "R46")
      (value "33k")
      (footprint "eagle-import:0603")
      (libsource (lib "eagle-import") (part "RES0603"))
    )
    (comp (ref "R47")
      (value "10k")
      (footprint "eagle-import:0603")
      (libsource (lib "eagle-import") (part "RES0603"))
    )
    (comp (ref "R48")
      (value "10k")
      (footprint "eagle-import:0603")
      (libsource (lib "eagle-import") (part "RES0603"))
    )
    (comp (ref "R49")
      (value "330")
      (footprint "eagle-import:0603")
      (libsource (lib "eagle-import") (part "RES0603"))
    )
    (comp (ref "R52")
      (value "1.0k")
      (footprint "eagle-import:0603")
      (libsource (lib "eagle-import") (part "RES0603"))
    )
    (comp (ref "R53")
      (value "1.0k")
      (footprint "eagle-import:0603")
      (libsource (lib "eagle-import") (part "RES0603"))
    )
    (comp (ref "R54")
      (value "1.0k")
      (footprint "eagle-import:0603")
      (libsource (lib "eagle-import") (part "RES0603"))
    )
    (comp (ref "S2")
      (value "SWITCH-DPDT/VER")
      (footprint "eagle-import:E-SWITCH-100-M7")
      (libsource (lib "eagle-import") (part "SWITCH-DPDT/VER"))
    )
    (comp (ref "T3")
      (value "MMBT3904")
      (footprint "eagle-import:SOT-23")
      (libsource (lib "eagle-import") (part "MMBT3904"))
    )
    (comp (ref "T4")
      (value "MMBT3904")
      (footprint "eagle-import:SOT-23")
      (libsource (lib "eagle-import") (part "MMBT3904"))
    )
    (comp (ref "TP9")
      (value "TESTPT")
      (footprint "eagle-import:1206TESTPAD")
      (libsource (lib "eagle-import") (part "TESTPT"))
    )
    (comp (ref "TP10")
      (value "TESTPT")
      (footprint "eagle-import:1206TESTPAD")
      (libsource (lib "eagle-import") (part "TESTPT"))
    )
    (comp (ref "TP11")
      (value "TESTPT")
      (footprint "eagle-import:1206TESTPAD")
      (libsource (lib "eagle-import") (part "TESTPT"))
    )
    (comp (ref "TP12")
      (value "TESTPT")
      (footprint "eagle-import:1206TESTPAD")
      (libsource (lib "eagle-import") (part "TESTPT"))
    )
    (comp (ref "TP13")
      (value "TESTPT")
      (footprint "eagle-import:1206TESTPAD")
      (libsource (lib "eagle-import") (part "TESTPT"))
    )
    (comp (ref "TP14")
      (value "TESTPT")
      (footprint "eagle-import:1206TESTPAD")
      (libsource (lib "eagle-import") (part "TESTPT"))
    )
    (comp (ref "X3")
      (value "BNC-H")
      (footprint "eagle-import:BNC90")
      (libsource (lib "eagle-import") (part "BNC-H"))
    )
    (comp (ref "X4")
      (value "BNC-H")
      (footprint "eagle-import:BNC90")
      (libsource (lib "eagle-import") (part "BNC-H"))
    )
  )
  (nets
    (net (code "1") (name "+1V_1") (class "Default")
      (node (ref "IC4") (pin "14") (pinfunction "B2_14") (pintype "bidirectional"))
      (node (ref "IC4") (pin "15") (pinfunction "W2_15") (pintype "bidirectional"))
      (node (ref "IC4") (pin "3") (pinfunction "W1_3") (pintype "bidirectional"))
      (node (ref "IC4") (pin "4") (pinfunction "B1_4") (pintype "bidirectional"))
      (node (ref "JP1") (pin "3") (pinfunction "3_3") (pintype "passive"))
      (node (ref "TP5") (pin "P$1") (pinfunction "P$1_P$1") (pintype "bidirectional"))
    )
    (net (code "2") (name "+1V_2") (class "Default")
      (node (ref "IC5") (pin "14") (pinfunction "B2_14") (pintype "bidirectional"))
      (node (ref "IC5") (pin "15") (pinfunction "W2_15") (pintype "bidirectional"))
      (node (ref "IC5") (pin "3") (pinfunction "W1_3") (pintype "bidirectional"))
      (node (ref "IC5") (pin "4") (pinfunction "B1_4") (pintype "bidirectional"))
      (node (ref "JP2") (pin "3") (pinfunction "3_3") (pintype "passive"))
      (node (ref "TP12") (pin "P$1") (pinfunction "P$1_P$1") (pintype "bidirectional"))
    )
    (net (code "3") (name "+1V_3") (class "Default")
      (node (ref "IC8") (pin "14") (pinfunction "B2_14") (pintype "bidirectional"))
      (node (ref "IC8") (pin "15") (pinfunction "W2_15") (pintype "bidirectional"))
      (node (ref "IC8") (pin "3") (pinfunction "W1_3") (pintype "bidirectional"))
      (node (ref "IC8") (pin "4") (pinfunction "B1_4") (pintype "bidirectional"))
      (node (ref "JP8") (pin "3") (pinfunction "3_3") (pintype "passive"))
      (node (ref "TP18") (pin "P$1") (pinfunction "P$1_P$1") (pintype "bidirectional"))
    )
    (net (code "4") (name "+1V_4") (class "Default")
      (node (ref "IC10") (pin "14") (pinfunction "B2_14") (pintype "bidirectional"))
      (node (ref "IC10") (pin "15") (pinfunction "W2_15") (pintype "bidirectional"))
      (node (ref "IC10") (pin "3") (pinfunction "W1_3") (pintype "bidirectional"))
      (node (ref "IC10") (pin "4") (pinfunction "B1_4") (pintype "bidirectional"))
      (node (ref "JP11") (pin "3") (pinfunction "3_3") (pintype "passive"))
      (node (ref "TP24") (pin "P$1") (pinfunction "P$1_P$1") (pintype "bidirectional"))
    )
    (net (code "5") (name "+5V") (class "Default")
      (node (ref "CP1") (pin "+") (pinfunction "+_+") (pintype "passive"))
      (node (ref "CP2") (pin "1") (pinfunction "1_1") (pintype "passive"))
      (node (ref "JP4") (pin "2") (pinfunction "2_2") (pintype "passive"))
      (node (ref "L4") (pin "2") (pinfunction "P$2_2") (pintype "passive"))
    )
    (net (code "6") (name "2.5V") (class "Default")
      (node (ref "C10") (pin "2") (pinfunction "P$2_2") (pintype "passive"))
      (node (ref "C14") (pin "2") (pinfunction "P$2_2") (pintype "passive"))
      (node (ref "IC6") (pin "2") (pinfunction "OUT_2") (pintype "bidirectional"))
      (node (ref "JP1") (pin "9") (pinfunction "9_9") (pintype "passive"))
      (node (ref "JP11") (pin "9") (pinfunction "9_9") (pintype "passive"))
      (node (ref "JP14") (pin "2") (pinfunction "2_2") (pintype "passive"))
      (node (ref "JP2") (pin "9") (pinfunction "9_9") (pintype "passive"))
      (node (ref "JP8") (pin "9") (pinfunction "9_9") (pintype "passive"))
      (node (ref "TP7") (pin "P$1") (pinfunction "P$1_P$1") (pintype "bidirectional"))
      (node (ref "U$1") (pin "AREF") (pinfunction "AREF_AREF") (pintype "power_in"))
    )
    (net (code "7") (name "ACT_T1") (class "Default")
      (node (ref "C11") (pin "2") (pinfunction "P$2_2") (pintype "passive"))
      (node (ref "R15") (pin "2") (pinfunction "P$2_2") (pintype "passive"))
      (node (ref "U$1") (pin "A11") (pinfunction "A11_A11") (pintype "bidirectional"))
    )
    (net (code "8") (name "ACT_T2") (class "Default")
      (node (ref "C7") (pin "2") (pinfunction "P$2_2") (pintype "passive"))
      (node (ref "R53") (pin "2") (pinfunction "P$2_2") (pintype "passive"))
      (node (ref "U$1") (pin "23/A9") (pinfunction "23/A9/T/PWM_23/A9") (pintype "bidirectional"))
    )
    (net (code "9") (name "ACT_T3") (class "Default")
      (node (ref "C5") (pin "2") (pinfunction "P$2_2") (pintype "passive"))
      (node (ref "R71") (pin "2") (pinfunction "P$2_2") (pintype "passive"))
      (node (ref "U$1") (pin "21/A7") (pinfunction "21/A7/PWM_21/A7") (pintype "bidirectional"))
    )
    (net (code "10") (name "ACT_T4") (class "Default")
      (node (ref "C8") (pin "2") (pinfunction "P$2_2") (pintype "passive"))
      (node (ref "R89") (pin "2") (pinfunction "P$2_2") (pintype "passive"))
      (node (ref "U$1") (pin "19/A5") (pinfunction "19/A5/T/SCL0_19/A5") (pintype "bidirectional"))
    )
    (net (code "11") (name "AGND") (class "Default")
      (node (ref "C10") (pin "1") (pinfunction "P$1_1") (pintype "passive"))
      (node (ref "C11") (pin "1") (pinfunction "P$1_1") (pintype "passive"))
      (node (ref "C12") (pin "1") (pinfunction "P$1_1") (pintype "passive"))
      (node (ref "C13") (pin "1") (pinfunction "P$1_1") (pintype "passive"))
      (node (ref "C14") (pin "1") (pinfunction "P$1_1") (pintype "passive"))
      (node (ref "C15") (pin "1") (pinfunction "P$1_1") (pintype "passive"))
      (node (ref "C20") (pin "1") (pinfunction "P$1_1") (pintype "passive"))
      (node (ref "C21") (pin "1") (pinfunction "P$1_1") (pintype "passive"))
      (node (ref "C22") (pin "1") (pinfunction "P$1_1") (pintype "passive"))
      (node (ref "C23") (pin "1") (pinfunction "P$1_1") (pintype "passive"))
      (node (ref "C24") (pin "1") (pinfunction "P$1_1") (pintype "passive"))
      (node (ref "C25") (pin "1") (pinfunction "P$1_1") (pintype "passive"))
      (node (ref "C27") (pin "1") (pinfunction "P$1_1") (pintype "passive"))
      (node (ref "C3") (pin "1") (pinfunction "P$1_1") (pintype "passive"))
      (node (ref "C30") (pin "1") (pinfunction "P$1_1") (pintype "passive"))
      (node (ref "C4") (pin "1") (pinfunction "P$1_1") (pintype "passive"))
      (node (ref "C5") (pin "1") (pinfunction "P$1_1") (pintype "passive"))
      (node (ref "C6") (pin "1") (pinfunction "P$1_1") (pintype "passive"))
      (node (ref "C7") (pin "1") (pinfunction "P$1_1") (pintype "passive"))
      (node (ref "C8") (pin "1") (pinfunction "P$1_1") (pintype "passive"))
      (node (ref "C9") (pin "1") (pinfunction "P$1_1") (pintype "passive"))
      (node (ref "CP1") (pin "-") (pinfunction "-_-") (pintype "passive"))
      (node (ref "CP2") (pin "2") (pinfunction "2_2") (pintype "passive"))
      (node (ref "CP3") (pin "-") (pinfunction "-_-") (pintype "passive"))
      (node (ref "IC1") (pin "4") (pinfunction "V-_4") (pintype "power_in"))
      (node (ref "IC10") (pin "11") (pinfunction "GND_11") (pintype "power_in"))
      (node (ref "IC2") (pin "4") (pinfunction "V-_4") (pintype "power_in"))
      (node (ref "IC3") (pin "3") (pinfunction "GND_3") (pintype "power_in"))
      (node (ref "IC4") (pin "11") (pinfunction "GND_11") (pintype "power_in"))
      (node (ref "IC5") (pin "11") (pinfunction "GND_11") (pintype "power_in"))
      (node (ref "IC6") (pin "3") (pinfunction "GND_3") (pintype "bidirectional"))
      (node (ref "IC7") (pin "4") (pinfunction "V-_4") (pintype "power_in"))
      (node (ref "IC8") (pin "11") (pinfunction "GND_11") (pintype "power_in"))
      (node (ref "IC9") (pin "4") (pinfunction "V-_4") (pintype "power_in"))
      (node (ref "JP1") (pin "12") (pinfunction "12_12") (pintype "passive"))
      (node (ref "JP10") (pin "2") (pinfunction "2_2") (pintype "passive"))
      (node (ref "JP11") (pin "12") (pinfunction "12_12") (pintype "passive"))
      (node (ref "JP12") (pin "2") (pinfunction "2_2") (pintype "passive"))
      (node (ref "JP13") (pin "2") (pinfunction "2_2") (pintype "passive"))
      (node (ref "JP2") (pin "12") (pinfunction "12_12") (pintype "passive"))
      (node (ref "JP3") (pin "2") (pinfunction "2_2") (pintype "passive"))
      (node (ref "JP4") (pin "1") (pinfunction "1_1") (pintype "passive"))
      (node (ref "JP5") (pin "2") (pinfunction "2_2") (pintype "passive"))
      (node (ref "JP6") (pin "2") (pinfunction "2_2") (pintype "passive"))
      (node (ref "JP7") (pin "2") (pinfunction "2_2") (pintype "passive"))
      (node (ref "JP8") (pin "12") (pinfunction "12_12") (pintype "passive"))
      (node (ref "JP9") (pin "2") (pinfunction "2_2") (pintype "passive"))
      (node (ref "L3") (pin "1") (pinfunction "P$1_1") (pintype "passive"))
      (node (ref "R1") (pin "1") (pinfunction "P$1_1") (pintype "passive"))
      (node (ref "R21") (pin "P$1") (pinfunction "1_P$1") (pintype "passive"))
      (node (ref "R23") (pin "P$1") (pinfunction "1_P$1") (pintype "passive"))
      (node (ref "R25") (pin "P$1") (pinfunction "1_P$1") (pintype "passive"))
      (node (ref "R27") (pin "P$1") (pinfunction "1_P$1") (pintype "passive"))
      (node (ref "R3") (pin "1") (pinfunction "P$1_1") (pintype "passive"))
      (node (ref "R37") (pin "1") (pinfunction "P$1_1") (pintype "passive"))
      (node (ref "R39") (pin "1") (pinfunction "P$1_1") (pintype "passive"))
      (node (ref "R41") (pin "P$2") (pinfunction "2_P$2") (pintype "passive"))
      (node (ref "R41") (pin "P$3") (pinfunction "3_P$3") (pintype "passive"))
      (node (ref "R42") (pin "P$2") (pinfunction "2_P$2") (pintype "passive"))
      (node (ref "R42") (pin "P$3") (pinfunction "3_P$3") (pintype "passive"))
      (node (ref "R55") (pin "1") (pinfunction "P$1_1") (pintype "passive"))
      (node (ref "R57") (pin "1") (pinfunction "P$1_1") (pintype "passive"))
      (node (ref "R59") (pin "P$2") (pinfunction "2_P$2") (pintype "passive"))
      (node (ref "R59") (pin "P$3") (pinfunction "3_P$3") (pintype "passive"))
      (node (ref "R6") (pin "P$2") (pinfunction "2_P$2") (pintype "passive"))
      (node (ref "R6") (pin "P$3") (pinfunction "3_P$3") (pintype "passive"))
      (node (ref "R60") (pin "P$2") (pinfunction "2_P$2") (pintype "passive"))
      (node (ref "R60") (pin "P$3") (pinfunction "3_P$3") (pintype "passive"))
      (node (ref "R7") (pin "P$2") (pinfunction "2_P$2") (pintype "passive"))
      (node (ref "R7") (pin "P$3") (pinfunction "3_P$3") (pintype "passive"))
      (node (ref "R73") (pin "1") (pinfunction "P$1_1") (pintype "passive"))
      (node (ref "R75") (pin "1") (pinfunction "P$1_1") (pintype "passive"))
      (node (ref "R77") (pin "P$2") (pinfunction "2_P$2") (pintype "passive"))
      (node (ref "R77") (pin "P$3") (pinfunction "3_P$3") (pintype "passive"))
      (node (ref "R78") (pin "P$2") (pinfunction "2_P$2") (pintype "passive"))
      (node (ref "R78") (pin "P$3") (pinfunction "3_P$3") (pintype "passive"))
      (node (ref "S1") (pin "P$2") (pinfunction "2_P$2") (pintype "bidirectional"))
      (node (ref "S1") (pin "P$5") (pinfunction "5_P$5") (pintype "bidirectional"))
      (node (ref "S2") (pin "P$2") (pinfunction "2_P$2") (pintype "bidirectional"))
      (node (ref "S2") (pin "P$5") (pinfunction "5_P$5") (pintype "bidirectional"))
      (node (ref "S3") (pin "P$2") (pinfunction "2_P$2") (pintype "bidirectional"))
      (node (ref "S3") (pin "P$5") (pinfunction "5_P$5") (pintype "bidirectional"))
      (node (ref "S4") (pin "P$2") (pinfunction "2_P$2") (pintype "bidirectional"))
      (node (ref "S4") (pin "P$5") (pinfunction "5_P$5") (pintype "bidirectional"))
      (node (ref "T1") (pin "2") (pinfunction "E_2") (pintype "passive"))
      (node (ref "T2") (pin "2") (pinfunction "E_2") (pintype "passive"))
      (node (ref "T3") (pin "2") (pinfunction "E_2") (pintype "passive"))
      (node (ref "T4") (pin "2") (pinfunction "E_2") (pintype "passive"))
      (node (ref "T5") (pin "2") (pinfunction "E_2") (pintype "passive"))
      (node (ref "T6") (pin "2") (pinfunction "E_2") (pintype "passive"))
      (node (ref "T7") (pin "2") (pinfunction "E_2") (pintype "passive"))
      (node (ref "T8") (pin "2") (pinfunction "E_2") (pintype "passive"))
      (node (ref "TP27") (pin "P$1") (pinfunction "P$1_P$1") (pintype "bidirectional"))
      (node (ref "U$1") (pin "AGND") (pinfunction "AGND_AGND") (pintype "power_in"))
      (node (ref "X1") (pin "2") (pinfunction "2_2") (pintype "passive"))
      (node (ref "X2") (pin "2") (pinfunction "2_2") (pintype "passive"))
      (node (ref "X3") (pin "2") (pinfunction "2_2") (pintype "passive"))
      (node (ref "X4") (pin "2") (pinfunction "2_2") (pintype "passive"))
      (node (ref "X5") (pin "2") (pinfunction "2_2") (pintype "passive"))
      (node (ref "X6") (pin "2") (pinfunction "2_2") (pintype "passive"))
      (node (ref "X7") (pin "2") (pinfunction "2_2") (pintype "passive"))
      (node (ref "X8") (pin "2") (pinfunction "2_2") (pintype "passive"))
    )
    (net (code "12") (name "CS_DAC") (class "Default")
      (node (ref "IC3") (pin "6") (pinfunction "SYNC_6") (pintype "bidirectional"))
      (node (ref "U$1") (pin "6") (pinfunction "6/PWM_6") (pintype "bidirectional"))
    )
    (net (code "13") (name "CS_LCD") (class "Default")
      (node (ref "LCD_HEADER") (pin "6") (pinfunction "6_6") (pintype "passive"))
      (node (ref "U$1") (pin "12") (pinfunction "12/MISO_12") (pintype "bidirectional"))
    )
    (net (code "14") (name "CS_POT1") (class "Default")
      (node (ref "IC4") (pin "9") (pinfunction "CS_9") (pintype "bidirectional"))
      (node (ref "U$1") (pin "2") (pinfunction "2_2") (pintype "bidirectional"))
    )
    (net (code "15") (name "CS_POT2") (class "Default")
      (node (ref "IC5") (pin "9") (pinfunction "CS_9") (pintype "bidirectional"))
      (node (ref "U$1") (pin "3") (pinfunction "3/CAN-TX/PWM_3") (pintype "bidirectional"))
    )
    (net (code "16") (name "CS_POT3") (class "Default")
      (node (ref "IC8") (pin "9") (pinfunction "CS_9") (pintype "bidirectional"))
      (node (ref "U$1") (pin "4") (pinfunction "4/CAN-RX-PWM_4") (pintype "bidirectional"))
    )
    (net (code "17") (name "CS_POT4") (class "Default")
      (node (ref "IC10") (pin "9") (pinfunction "CS_9") (pintype "bidirectional"))
      (node (ref "U$1") (pin "5") (pinfunction "5/PWM_5") (pintype "bidirectional"))
    )
    (net (code "18") (name "ENC_A1") (class "Default")
      (node (ref "C17") (pin "2") (pinfunction "2_2") (pintype "passive"))
      (node (ref "ENC1") (pin "A") (pinfunction "A_A") (pintype "bidirectional"))
      (node (ref "R28") (pin "P$1") (pinfunction "1_P$1") (pintype "passive"))
      (node (ref "U$1") (pin "17/A3") (pinfunction "17/A3/T_17/A3") (pintype "bidirectional"))
    )
    (net (code "19") (name "ENC_A2") (class "Default")
      (node (ref "C19") (pin "2") (pinfunction "2_2") (pintype "passive"))
      (node (ref "ENC2") (pin "A") (pinfunction "A_A") (pintype "bidirectional"))
      (node (ref "R33") (pin "P$1") (pinfunction "1_P$1") (pintype "passive"))
      (node (ref "U$1") (pin "14/A0") (pinfunction "14/A0_14/A0") (pintype "bidirectional"))
    )
    (net (code "20") (name "ENC_B1") (class "Default")
      (node (ref "C16") (pin "2") (pinfunction "2_2") (pintype "passive"))
      (node (ref "ENC1") (pin "B") (pinfunction "B_B") (pintype "bidirectional"))
      (node (ref "R19") (pin "1") (pinfunction "P$1_1") (pintype "passive"))
      (node (ref "U$1") (pin "7") (pinfunction "7/RX3_7") (pintype "bidirectional"))
    )
    (net (code "21") (name "ENC_B2") (class "Default")
      (node (ref "C18") (pin "2") (pinfunction "2_2") (pintype "passive"))
      (node (ref "ENC2") (pin "B") (pinfunction "B_B") (pintype "bidirectional"))
      (node (ref "R32") (pin "1") (pinfunction "P$1_1") (pintype "passive"))
      (node (ref "U$1") (pin "16/A2") (pinfunction "16/A2/T_16/A2") (pintype "bidirectional"))
    )
    (net (code "22") (name "ENC_SW1") (class "Default")
      (node (ref "ENC1") (pin "E") (pinfunction "E_E") (pintype "bidirectional"))
      (node (ref "R29") (pin "1") (pinfunction "P$1_1") (pintype "passive"))
      (node (ref "U$1") (pin "8") (pinfunction "8/TX3_8") (pintype "bidirectional"))
    )
    (net (code "23") (name "ENC_SW2") (class "Default")
      (node (ref "ENC2") (pin "E") (pinfunction "E_E") (pintype "bidirectional"))
      (node (ref "R34") (pin "1") (pinfunction "P$1_1") (pintype "passive"))
      (node (ref "U$1") (pin "15/A1") (pinfunction "15/A1/T_15/A1") (pintype "bidirectional"))
    )
    (net (code "24") (name "GND") (class "Default")
      (node (ref "C1") (pin "1") (pinfunction "P$1_1") (pintype "passive"))
      (node (ref "C16") (pin "1") (pinfunction "1_1") (pintype "passive"))
      (node (ref "C17") (pin "1") (pinfunction "1_1") (pintype "passive"))
      (node (ref "C18") (pin "1") (pinfunction "1_1") (pintype "passive"))
      (node (ref "C19") (pin "1") (pinfunction "1_1") (pintype "passive"))
      (node (ref "C2") (pin "1") (pinfunction "P$1_1") (pintype "passive"))
      (node (ref "IC10") (pin "12") (pinfunction "VSS_12") (pintype "power_in"))
      (node (ref "IC4") (pin "12") (pinfunction "VSS_12") (pintype "power_in"))
      (node (ref "IC5") (pin "12") (pinfunction "VSS_12") (pintype "power_in"))
      (node (ref "IC8") (pin "12") (pinfunction "VSS_12") (pintype "power_in"))
      (node (ref "L3") (pin "2") (pinfunction "P$2_2") (pintype "passive"))
      (node (ref "LCD_HEADER") (pin "2") (pinfunction "2_2") (pintype "passive"))
      (node (ref "LCD_HEADER") (pin "4") (pinfunction "4_4") (pintype "passive"))
      (node (ref "R30") (pin "1") (pinfunction "P$1_1") (pintype "passive"))
      (node (ref "R31") (pin "1") (pinfunction "P$1_1") (pintype "passive"))
      (node (ref "R35") (pin "1") (pinfunction "P$1_1") (pintype "passive"))
      (node (ref "R36") (pin "1") (pinfunction "P$1_1") (pintype "passive"))
      (node (ref "U$1") (pin "GND") (pinfunction "GND_GND") (pintype "power_in"))
      (node (ref "U$1") (pin "GND1") (pinfunction "GND_GND1") (pintype "power_in"))
    )
    (net (code "25") (name "I1") (class "Default")
      (node (ref "IC4") (pin "16") (pinfunction "A2_16") (pintype "bidirectional"))
      (node (ref "JP1") (pin "5") (pinfunction "5_5") (pintype "passive"))
      (node (ref "TP6") (pin "P$1") (pinfunction "P$1_P$1") (pintype "bidirectional"))
    )
    (net (code "26") (name "I2") (class "Default")
      (node (ref "IC5") (pin "16") (pinfunction "A2_16") (pintype "bidirectional"))
      (node (ref "JP2") (pin "5") (pinfunction "5_5") (pintype "passive"))
      (node (ref "TP13") (pin "P$1") (pinfunction "P$1_P$1") (pintype "bidirectional"))
    )
    (net (code "27") (name "I3") (class "Default")
      (node (ref "IC8") (pin "16") (pinfunction "A2_16") (pintype "bidirectional"))
      (node (ref "JP8") (pin "5") (pinfunction "5_5") (pintype "passive"))
      (node (ref "TP19") (pin "P$1") (pinfunction "P$1_P$1") (pintype "bidirectional"))
    )
    (net (code "28") (name "I4") (class "Default")
      (node (ref "IC10") (pin "16") (pinfunction "A2_16") (pintype "bidirectional"))
      (node (ref "JP11") (pin "5") (pinfunction "5_5") (pintype "passive"))
      (node (ref "TP25") (pin "P$1") (pinfunction "P$1_P$1") (pintype "bidirectional"))
    )
    (net (code "29") (name "LIMA1") (class "Default")
      (node (ref "JP1") (pin "4") (pinfunction "4_4") (pintype "passive"))
      (node (ref "R2") (pin "2") (pinfunction "P$2_2") (pintype "passive"))
      (node (ref "T1") (pin "3") (pinfunction "C_3") (pintype "passive"))
    )
    (net (code "30") (name "LIMA2") (class "Default")
      (node (ref "JP2") (pin "4") (pinfunction "4_4") (pintype "passive"))
      (node (ref "R38") (pin "2") (pinfunction "P$2_2") (pintype "passive"))
      (node (ref "T3") (pin "3") (pinfunction "C_3") (pintype "passive"))
    )
    (net (code "31") (name "LIMA3") (class "Default")
      (node (ref "JP8") (pin "4") (pinfunction "4_4") (pintype "passive"))
      (node (ref "R56") (pin "2") (pinfunction "P$2_2") (pintype "passive"))
      (node (ref "T5") (pin "3") (pinfunction "C_3") (pintype "passive"))
    )
    (net (code "32") (name "LIMA4") (class "Default")
      (node (ref "JP11") (pin "4") (pinfunction "4_4") (pintype "passive"))
      (node (ref "R74") (pin "2") (pinfunction "P$2_2") (pintype "passive"))
      (node (ref "T7") (pin "3") (pinfunction "C_3") (pintype "passive"))
    )
    (net (code "33") (name "LIMB1") (class "Default")
      (node (ref "JP1") (pin "6") (pinfunction "6_6") (pintype "passive"))
      (node (ref "R4") (pin "2") (pinfunction "P$2_2") (pintype "passive"))
      (node (ref "T2") (pin "3") (pinfunction "C_3") (pintype "passive"))
    )
    (net (code "34") (name "LIMB2") (class "Default")
      (node (ref "JP2") (pin "6") (pinfunction "6_6") (pintype "passive"))
      (node (ref "R40") (pin "2") (pinfunction "P$2_2") (pintype "passive"))
      (node (ref "T4") (pin "3") (pinfunction "C_3") (pintype "passive"))
    )
    (net (code "35") (name "LIMB3") (class "Default")
      (node (ref "JP8") (pin "6") (pinfunction "6_6") (pintype "passive"))
      (node (ref "R58") (pin "2") (pinfunction "P$2_2") (pintype "passive"))
      (node (ref "T6") (pin "3") (pinfunction "C_3") (pintype "passive"))
    )
    (net (code "36") (name "LIMB4") (class "Default")
      (node (ref "JP11") (pin "6") (pinfunction "6_6") (pintype "passive"))
      (node (ref "R76") (pin "2") (pinfunction "P$2_2") (pintype "passive"))
      (node (ref "T8") (pin "3") (pinfunction "C_3") (pintype "passive"))
    )
    (net (code "37") (name "MOSI") (class "Default")
      (node (ref "LCD_HEADER") (pin "3") (pinfunction "3_3") (pintype "passive"))
      (node (ref "U$1") (pin "11") (pinfunction "11/MOSI_11") (pintype "bidirectional"))
    )
    (net (code "38") (name "MOSI_B") (class "Default")
      (node (ref "IC10") (pin "8") (pinfunction "SDI_8") (pintype "bidirectional"))
      (node (ref "IC3") (pin "8") (pinfunction "DIN_8") (pintype "bidirectional"))
      (node (ref "IC4") (pin "8") (pinfunction "SDI_8") (pintype "bidirectional"))
      (node (ref "IC5") (pin "8") (pinfunction "SDI_8") (pintype "bidirectional"))
      (node (ref "IC8") (pin "8") (pinfunction "SDI_8") (pintype "bidirectional"))
      (node (ref "U$1") (pin "0") (pinfunction "0/RX1/T_0") (pintype "bidirectional"))
    )
    (net (code "39") (name "Net-(C1-P$2)") (class "Default")
      (node (ref "C1") (pin "2") (pinfunction "P$2_2") (pintype "passive"))
      (node (ref "C2") (pin "2") (pinfunction "P$2_2") (pintype "passive"))
      (node (ref "L2") (pin "1") (pinfunction "P$1_1") (pintype "passive"))
      (node (ref "U$1") (pin "VIN") (pinfunction "VIN_VIN") (pintype "power_in"))
    )
    (net (code "40") (name "Net-(C27-P$2)") (class "Default")
      (node (ref "C27") (pin "2") (pinfunction "P$2_2") (pintype "passive"))
      (node (ref "C30") (pin "2") (pinfunction "P$2_2") (pintype "passive"))
      (node (ref "IC3") (pin "9") (pinfunction "VDD_9") (pintype "power_in"))
      (node (ref "L1") (pin "1") (pinfunction "P$1_1") (pintype "passive"))
    )
    (net (code "41") (name "Net-(ENC1-GND)") (class "Default")
      (node (ref "ENC1") (pin "C") (pinfunction "GND_C") (pintype "bidirectional"))
      (node (ref "R30") (pin "2") (pinfunction "P$2_2") (pintype "passive"))
    )
    (net (code "42") (name "Net-(ENC2-GND)") (class "Default")
      (node (ref "ENC2") (pin "C") (pinfunction "GND_C") (pintype "bidirectional"))
      (node (ref "R35") (pin "2") (pinfunction "P$2_2") (pintype "passive"))
    )
    (net (code "43") (name "Net-(IC1A--IN)") (class "Default")
      (node (ref "IC1") (pin "2") (pinfunction "-IN_2") (pintype "input"))
      (node (ref "R6") (pin "P$1") (pinfunction "1_P$1") (pintype "passive"))
      (node (ref "R8") (pin "1") (pinfunction "P$1_1") (pintype "passive"))
      (node (ref "TP2") (pin "P$1") (pinfunction "P$1_P$1") (pintype "bidirectional"))
    )
    (net (code "44") (name "Net-(IC1A-OUT)") (class "Default")
      (node (ref "IC1") (pin "1") (pinfunction "OUT_1") (pintype "output"))
      (node (ref "R10") (pin "2") (pinfunction "P$2_2") (pintype "passive"))
      (node (ref "R9") (pin "1") (pinfunction "P$1_1") (pintype "passive"))
    )
    (net (code "45") (name "Net-(IC1B-+IN)") (class "Default")
      (node (ref "IC1") (pin "5") (pinfunction "+IN_5") (pintype "input"))
      (node (ref "R11") (pin "1") (pinfunction "P$1_1") (pintype "passive"))
      (node (ref "R7") (pin "P$1") (pinfunction "1_P$1") (pintype "passive"))
      (node (ref "TP3") (pin "P$1") (pinfunction "P$1_P$1") (pintype "bidirectional"))
    )
    (net (code "46") (name "Net-(IC1B-OUT)") (class "Default")
      (node (ref "IC1") (pin "7") (pinfunction "OUT_7") (pintype "output"))
      (node (ref "R12") (pin "1") (pinfunction "P$1_1") (pintype "passive"))
      (node (ref "R13") (pin "2") (pinfunction "P$2_2") (pintype "passive"))
    )
    (net (code "47") (name "Net-(IC2A--IN)") (class "Default")
      (node (ref "IC2") (pin "2") (pinfunction "-IN_2") (pintype "input"))
      (node (ref "R41") (pin "P$1") (pinfunction "1_P$1") (pintype "passive"))
      (node (ref "R43") (pin "1") (pinfunction "P$1_1") (pintype "passive"))
      (node (ref "TP9") (pin "P$1") (pinfunction "P$1_P$1") (pintype "bidirectional"))
    )
    (net (code "48") (name "Net-(IC2A-OUT)") (class "Default")
      (node (ref "IC2") (pin "1") (pinfunction "OUT_1") (pintype "output"))
      (node (ref "R44") (pin "1") (pinfunction "P$1_1") (pintype "passive"))
      (node (ref "R45") (pin "2") (pinfunction "P$2_2") (pintype "passive"))
    )
    (net (code "49") (name "Net-(IC2B-+IN)") (class "Default")
      (node (ref "IC2") (pin "5") (pinfunction "+IN_5") (pintype "input"))
      (node (ref "R42") (pin "P$1") (pinfunction "1_P$1") (pintype "passive"))
      (node (ref "R46") (pin "1") (pinfunction "P$1_1") (pintype "passive"))
      (node (ref "TP10") (pin "P$1") (pinfunction "P$1_P$1") (pintype "bidirectional"))
    )
    (net (code "50") (name "Net-(IC2B-OUT)") (class "Default")
      (node (ref "IC2") (pin "7") (pinfunction "OUT_7") (pintype "output"))
      (node (ref "R47") (pin "1") (pinfunction "P$1_1") (pintype "passive"))
      (node (ref "R48") (pin "2") (pinfunction "P$2_2") (pintype "passive"))
    )
    (net (code "51") (name "Net-(IC3-VREF)") (class "Default")
      (node (ref "IC3") (pin "10") (pinfunction "VREF_10") (pintype "bidirectional"))
      (node (ref "JP14") (pin "1") (pinfunction "1_1") (pintype "passive"))
      (node (ref "TP1") (pin "P$1") (pinfunction "P$1_P$1") (pintype "bidirectional"))
    )
    (net (code "52") (name "Net-(IC7A--IN)") (class "Default")
      (node (ref "IC7") (pin "2") (pinfunction "-IN_2") (pintype "input"))
      (node (ref "R59") (pin "P$1") (pinfunction "1_P$1") (pintype "passive"))
      (node (ref "R61") (pin "1") (pinfunction "P$1_1") (pintype "passive"))
      (node (ref "TP15") (pin "P$1") (pinfunction "P$1_P$1") (pintype "bidirectional"))
    )
    (net (code "53") (name "Net-(IC7A-OUT)") (class "Default")
      (node (ref "IC7") (pin "1") (pinfunction "OUT_1") (pintype "output"))
      (node (ref "R62") (pin "1") (pinfunction "P$1_1") (pintype "passive"))
      (node (ref "R63") (pin "2") (pinfunction "P$2_2") (pintype "passive"))
    )
    (net (code "54") (name "Net-(IC7B-+IN)") (class "Default")
      (node (ref "IC7") (pin "5") (pinfunction "+IN_5") (pintype "input"))
      (node (ref "R60") (pin "P$1") (pinfunction "1_P$1") (pintype "passive"))
      (node (ref "R64") (pin "1") (pinfunction "P$1_1") (pintype "passive"))
      (node (ref "TP16") (pin "P$1") (pinfunction "P$1_P$1") (pintype "bidirectional"))
    )
    (net (code "55") (name "Net-(IC7B-OUT)") (class "Default")
      (node (ref "IC7") (pin "7") (pinfunction "OUT_7") (pintype "output"))
      (node (ref "R65") (pin "1") (pinfunction "P$1_1") (pintype "passive"))
      (node (ref "R66") (pin "2") (pinfunction "P$2_2") (pintype "passive"))
    )
    (net (code "56") (name "Net-(IC9A--IN)") (class "Default")
      (node (ref "IC9") (pin "2") (pinfunction "-IN_2") (pintype "input"))
      (node (ref "R77") (pin "P$1") (pinfunction "1_P$1") (pintype "passive"))
      (node (ref "R79") (pin "1") (pinfunction "P$1_1") (pintype "passive"))
      (node (ref "TP21") (pin "P$1") (pinfunction "P$1_P$1") (pintype "bidirectional"))
    )
    (net (code "57") (name "Net-(IC9A-OUT)") (class "Default")
      (node (ref "IC9") (pin "1") (pinfunction "OUT_1") (pintype "output"))
      (node (ref "R80") (pin "1") (pinfunction "P$1_1") (pintype "passive"))
      (node (ref "R81") (pin "2") (pinfunction "P$2_2") (pintype "passive"))
    )
    (net (code "58") (name "Net-(IC9B-+IN)") (class "Default")
      (node (ref "IC9") (pin "5") (pinfunction "+IN_5") (pintype "input"))
      (node (ref "R78") (pin "P$1") (pinfunction "1_P$1") (pintype "passive"))
      (node (ref "R82") (pin "1") (pinfunction "P$1_1") (pintype "passive"))
      (node (ref "TP22") (pin "P$1") (pinfunction "P$1_P$1") (pintype "bidirectional"))
    )
    (net (code "59") (name "Net-(IC9B-OUT)") (class "Default")
      (node (ref "IC9") (pin "7") (pinfunction "OUT_7") (pintype "output"))
      (node (ref "R83") (pin "1") (pinfunction "P$1_1") (pintype "passive"))
      (node (ref "R84") (pin "2") (pinfunction "P$2_2") (pintype "passive"))
    )
    (net (code "60") (name "Net-(LCD_HEADER-Pad1)") (class "Default")
      (node (ref "LCD_HEADER") (pin "1") (pinfunction "1_1") (pintype "passive"))
      (node (ref "U$1") (pin "3.3V") (pinfunction "3.3V_3.3V") (pintype "power_in"))
      (node (ref "U$1") (pin "3.3V1") (pinfunction "3.3V_3.3V1") (pintype "power_in"))
    )
    (net (code "61") (name "Net-(R1-P$2)") (class "Default")
      (node (ref "JP3") (pin "1") (pinfunction "1_1") (pintype "passive"))
      (node (ref "R1") (pin "2") (pinfunction "P$2_2") (pintype "passive"))
      (node (ref "R2") (pin "1") (pinfunction "P$1_1") (pintype "passive"))
      (node (ref "S1") (pin "P$3") (pinfunction "3_P$3") (pintype "bidirectional"))
    )
    (net (code "62") (name "Net-(R3-P$2)") (class "Default")
      (node (ref "JP5") (pin "1") (pinfunction "1_1") (pintype "passive"))
      (node (ref "R3") (pin "2") (pinfunction "P$2_2") (pintype "passive"))
      (node (ref "R4") (pin "1") (pinfunction "P$1_1") (pintype "passive"))
      (node (ref "S1") (pin "P$6") (pinfunction "6_P$6") (pintype "bidirectional"))
    )
    (net (code "63") (name "Net-(R5-P$1)") (class "Default")
      (node (ref "R5") (pin "1") (pinfunction "P$1_1") (pintype "passive"))
      (node (ref "S1") (pin "P$4") (pinfunction "4_P$4") (pintype "bidirectional"))
    )
    (net (code "64") (name "Net-(R5-P$2)") (class "Default")
      (node (ref "D1") (pin "C") (pinfunction "C_C") (pintype "bidirectional"))
      (node (ref "R5") (pin "2") (pinfunction "P$2_2") (pintype "passive"))
    )
    (net (code "65") (name "Net-(R10-P$1)") (class "Default")
      (node (ref "R10") (pin "1") (pinfunction "P$1_1") (pintype "passive"))
      (node (ref "T1") (pin "1") (pinfunction "B_1") (pintype "passive"))
    )
    (net (code "66") (name "Net-(R13-P$1)") (class "Default")
      (node (ref "R13") (pin "1") (pinfunction "P$1_1") (pintype "passive"))
      (node (ref "T2") (pin "1") (pinfunction "B_1") (pintype "passive"))
    )
    (net (code "67") (name "Net-(R14-P$1)") (class "Default")
      (node (ref "JP1") (pin "8") (pinfunction "8_8") (pintype "passive"))
      (node (ref "R14") (pin "1") (pinfunction "P$1_1") (pintype "passive"))
      (node (ref "R15") (pin "1") (pinfunction "P$1_1") (pintype "passive"))
    )
    (net (code "68") (name "Net-(R14-P$2)") (class "Default")
      (node (ref "R14") (pin "2") (pinfunction "P$2_2") (pintype "passive"))
      (node (ref "X1") (pin "1") (pinfunction "1_1") (pintype "passive"))
    )
    (net (code "69") (name "Net-(R18-P$2)") (class "Default")
      (node (ref "R18") (pin "2") (pinfunction "P$2_2") (pintype "passive"))
      (node (ref "X2") (pin "1") (pinfunction "1_1") (pintype "passive"))
    )
    (net (code "70") (name "Net-(R31-P$2)") (class "Default")
      (node (ref "ENC1") (pin "D") (pinfunction "D_D") (pintype "bidirectional"))
      (node (ref "R31") (pin "2") (pinfunction "P$2_2") (pintype "passive"))
    )
    (net (code "71") (name "Net-(R36-P$2)") (class "Default")
      (node (ref "ENC2") (pin "D") (pinfunction "D_D") (pintype "bidirectional"))
      (node (ref "R36") (pin "2") (pinfunction "P$2_2") (pintype "passive"))
    )
    (net (code "72") (name "Net-(R37-P$2)") (class "Default")
      (node (ref "JP6") (pin "1") (pinfunction "1_1") (pintype "passive"))
      (node (ref "R37") (pin "2") (pinfunction "P$2_2") (pintype "passive"))
      (node (ref "R38") (pin "1") (pinfunction "P$1_1") (pintype "passive"))
      (node (ref "S2") (pin "P$3") (pinfunction "3_P$3") (pintype "bidirectional"))
    )
    (net (code "73") (name "Net-(R39-P$2)") (class "Default")
      (node (ref "JP7") (pin "1") (pinfunction "1_1") (pintype "passive"))
      (node (ref "R39") (pin "2") (pinfunction "P$2_2") (pintype "passive"))
      (node (ref "R40") (pin "1") (pinfunction "P$1_1") (pintype "passive"))
      (node (ref "S2") (pin "P$6") (pinfunction "6_P$6") (pintype "bidirectional"))
    )
    (net (code "74") (name "Net-(R45-P$1)") (class "Default")
      (node (ref "R45") (pin "1") (pinfunction "P$1_1") (pintype "passive"))
      (node (ref "T3") (pin "1") (pinfunction "B_1") (pintype "passive"))
    )
    (net (code "75") (name "Net-(R48-P$1)") (class "Default")
      (node (ref "R48") (pin "1") (pinfunction "P$1_1") (pintype "passive"))
      (node (ref "T4") (pin "1") (pinfunction "B_1") (pintype "passive"))
    )
    (net (code "76") (name "Net-(R49-P$1)") (class "Default")
      (node (ref "R49") (pin "1") (pinfunction "P$1_1") (pintype "passive"))
      (node (ref "S2") (pin "P$4") (pinfunction "4_P$4") (pintype "bidirectional"))
    )
    (net (code "77") (name "Net-(R49-P$2)") (class "Default")
      (node (ref "D2") (pin "C") (pinfunction "C_C") (pintype "bidirectional"))
      (node (ref "R49") (pin "2") (pinfunction "P$2_2") (pintype "passive"))
    )
    (net (code "78") (name "Net-(R52-P$1)") (class "Default")
      (node (ref "JP2") (pin "8") (pinfunction "8_8") (pintype "passive"))
      (node (ref "R52") (pin "1") (pinfunction "P$1_1") (pintype "passive"))
      (node (ref "R53") (pin "1") (pinfunction "P$1_1") (pintype "passive"))
    )
    (net (code "79") (name "Net-(R52-P$2)") (class "Default")
      (node (ref "R52") (pin "2") (pinfunction "P$2_2") (pintype "passive"))
      (node (ref "X3") (pin "1") (pinfunction "1_1") (pintype "passive"))
    )
    (net (code "80") (name "Net-(R54-P$2)") (class "Default")
      (node (ref "R54") (pin "2") (pinfunction "P$2_2") (pintype "passive"))
      (node (ref "X4") (pin "1") (pinfunction "1_1") (pintype "passive"))
    )
    (net (code "81") (name "Net-(R55-P$2)") (class "Default")
      (node (ref "JP9") (pin "1") (pinfunction "1_1") (pintype "passive"))
      (node (ref "R55") (pin "2") (pinfunction "P$2_2") (pintype "passive"))
      (node (ref "R56") (pin "1") (pinfunction "P$1_1") (pintype "passive"))
      (node (ref "S3") (pin "P$3") (pinfunction "3_P$3") (pintype "bidirectional"))
    )
    (net (code "82") (name "Net-(R57-P$2)") (class "Default")
      (node (ref "JP10") (pin "1") (pinfunction "1_1") (pintype "passive"))
      (node (ref "R57") (pin "2") (pinfunction "P$2_2") (pintype "passive"))
      (node (ref "R58") (pin "1") (pinfunction "P$1_1") (pintype "passive"))
      (node (ref "S3") (pin "P$6") (pinfunction "6_P$6") (pintype "bidirectional"))
    )
    (net (code "83") (name "Net-(R63-P$1)") (class "Default")
      (node (ref "R63") (pin "1") (pinfunction "P$1_1") (pintype "passive"))
      (node (ref "T5") (pin "1") (pinfunction "B_1") (pintype "passive"))
    )
    (net (code "84") (name "Net-(R66-P$1)") (class "Default")
      (node (ref "R66") (pin "1") (pinfunction "P$1_1") (pintype "passive"))
      (node (ref "T6") (pin "1") (pinfunction "B_1") (pintype "passive"))
    )
    (net (code "85") (name "Net-(R67-P$1)") (class "Default")
      (node (ref "R67") (pin "1") (pinfunction "P$1_1") (pintype "passive"))
      (node (ref "S3") (pin "P$4") (pinfunction "4_P$4") (pintype "bidirectional"))
    )
    (net (code "86") (name "Net-(R67-P$2)") (class "Default")
      (node (ref "D3") (pin "C") (pinfunction "C_C") (pintype "bidirectional"))
      (node (ref "R67") (pin "2") (pinfunction "P$2_2") (pintype "passive"))
    )
    (net (code "87") (name "Net-(R70-P$1)") (class "Default")
      (node (ref "JP8") (pin "8") (pinfunction "8_8") (pintype "passive"))
      (node (ref "R70") (pin "1") (pinfunction "P$1_1") (pintype "passive"))
      (node (ref "R71") (pin "1") (pinfunction "P$1_1") (pintype "passive"))
    )
    (net (code "88") (name "Net-(R70-P$2)") (class "Default")
      (node (ref "R70") (pin "2") (pinfunction "P$2_2") (pintype "passive"))
      (node (ref "X5") (pin "1") (pinfunction "1_1") (pintype "passive"))
    )
    (net (code "89") (name "Net-(R72-P$2)") (class "Default")
      (node (ref "R72") (pin "2") (pinfunction "P$2_2") (pintype "passive"))
      (node (ref "X6") (pin "1") (pinfunction "1_1") (pintype "passive"))
    )
    (net (code "90") (name "Net-(R73-P$2)") (class "Default")
      (node (ref "JP12") (pin "1") (pinfunction "1_1") (pintype "passive"))
      (node (ref "R73") (pin "2") (pinfunction "P$2_2") (pintype "passive"))
      (node (ref "R74") (pin "1") (pinfunction "P$1_1") (pintype "passive"))
      (node (ref "S4") (pin "P$3") (pinfunction "3_P$3") (pintype "bidirectional"))
    )
    (net (code "91") (name "Net-(R75-P$2)") (class "Default")
      (node (ref "JP13") (pin "1") (pinfunction "1_1") (pintype "passive"))
      (node (ref "R75") (pin "2") (pinfunction "P$2_2") (pintype "passive"))
      (node (ref "R76") (pin "1") (pinfunction "P$1_1") (pintype "passive"))
      (node (ref "S4") (pin "P$6") (pinfunction "6_P$6") (pintype "bidirectional"))
    )
    (net (code "92") (name "Net-(R81-P$1)") (class "Default")
      (node (ref "R81") (pin "1") (pinfunction "P$1_1") (pintype "passive"))
      (node (ref "T7") (pin "1") (pinfunction "B_1") (pintype "passive"))
    )
    (net (code "93") (name "Net-(R84-P$1)") (class "Default")
      (node (ref "R84") (pin "1") (pinfunction "P$1_1") (pintype "passive"))
      (node (ref "T8") (pin "1") (pinfunction "B_1") (pintype "passive"))
    )
    (net (code "94") (name "Net-(R85-P$1)") (class "Default")
      (node (ref "R85") (pin "1") (pinfunction "P$1_1") (pintype "passive"))
      (node (ref "S4") (pin "P$4") (pinfunction "4_P$4") (pintype "bidirectional"))
    )
    (net (code "95") (name "Net-(R85-P$2)") (class "Default")
      (node (ref "D4") (pin "C") (pinfunction "C_C") (pintype "bidirectional"))
      (node (ref "R85") (pin "2") (pinfunction "P$2_2") (pintype "passive"))
    )
    (net (code "96") (name "Net-(R88-P$1)") (class "Default")
      (node (ref "JP11") (pin "8") (pinfunction "8_8") (pintype "passive"))
      (node (ref "R88") (pin "1") (pinfunction "P$1_1") (pintype "passive"))
      (node (ref "R89") (pin "1") (pinfunction "P$1_1") (pintype "passive"))
    )
    (net (code "97") (name "Net-(R88-P$2)") (class "Default")
      (node (ref "R88") (pin "2") (pinfunction "P$2_2") (pintype "passive"))
      (node (ref "X7") (pin "1") (pinfunction "1_1") (pintype "passive"))
    )
    (net (code "98") (name "Net-(R90-P$2)") (class "Default")
      (node (ref "R90") (pin "2") (pinfunction "P$2_2") (pintype "passive"))
      (node (ref "X8") (pin "1") (pinfunction "1_1") (pintype "passive"))
    )
    (net (code "99") (name "P1") (class "Default")
      (node (ref "IC4") (pin "2") (pinfunction "A1_2") (pintype "bidirectional"))
      (node (ref "JP1") (pin "1") (pinfunction "1_1") (pintype "passive"))
      (node (ref "TP4") (pin "P$1") (pinfunction "P$1_P$1") (pintype "bidirectional"))
    )
    (net (code "100") (name "P2") (class "Default")
      (node (ref "IC5") (pin "2") (pinfunction "A1_2") (pintype "bidirectional"))
      (node (ref "JP2") (pin "1") (pinfunction "1_1") (pintype "passive"))
      (node (ref "TP11") (pin "P$1") (pinfunction "P$1_P$1") (pintype "bidirectional"))
    )
    (net (code "101") (name "P3") (class "Default")
      (node (ref "IC8") (pin "2") (pinfunction "A1_2") (pintype "bidirectional"))
      (node (ref "JP8") (pin "1") (pinfunction "1_1") (pintype "passive"))
      (node (ref "TP17") (pin "P$1") (pinfunction "P$1_P$1") (pintype "bidirectional"))
    )
    (net (code "102") (name "P4") (class "Default")
      (node (ref "IC10") (pin "2") (pinfunction "A1_2") (pintype "bidirectional"))
      (node (ref "JP11") (pin "1") (pinfunction "1_1") (pintype "passive"))
      (node (ref "TP23") (pin "P$1") (pinfunction "P$1_P$1") (pintype "bidirectional"))
    )
    (net (code "103") (name "RST_LCD") (class "Default")
      (node (ref "LCD_HEADER") (pin "8") (pinfunction "8_8") (pintype "passive"))
      (node (ref "U$1") (pin "9") (pinfunction "9/RX2/PWM_9") (pintype "bidirectional"))
    )
    (net (code "104") (name "RS_LCD") (class "Default")
      (node (ref "LCD_HEADER") (pin "7") (pinfunction "7_7") (pintype "passive"))
      (node (ref "U$1") (pin "10") (pinfunction "10/TX2/PWM_10") (pintype "bidirectional"))
    )
    (net (code "105") (name "SCK") (class "Default")
      (node (ref "LCD_HEADER") (pin "5") (pinfunction "5_5") (pintype "passive"))
      (node (ref "U$1") (pin "13") (pinfunction "13/SCK/LED_13") (pintype "bidirectional"))
    )
    (net (code "106") (name "SCK_B") (class "Default")
      (node (ref "IC10") (pin "7") (pinfunction "CLK_7") (pintype "bidirectional"))
      (node (ref "IC3") (pin "7") (pinfunction "SCLK_7") (pintype "bidirectional"))
      (node (ref "IC4") (pin "7") (pinfunction "CLK_7") (pintype "bidirectional"))
      (node (ref "IC5") (pin "7") (pinfunction "CLK_7") (pintype "bidirectional"))
      (node (ref "IC8") (pin "7") (pinfunction "CLK_7") (pintype "bidirectional"))
      (node (ref "U$1") (pin "1") (pinfunction "1/TX1/T_1") (pintype "bidirectional"))
    )
    (net (code "107") (name "VBAT") (class "Default")
      (node (ref "U$1") (pin "VBAT") (pinfunction "VBAT_VBAT") (pintype "power_in"))
    )
    (net (code "108") (name "VDD") (class "Default")
      (node (ref "C12") (pin "2") (pinfunction "P$2_2") (pintype "passive"))
      (node (ref "C13") (pin "2") (pinfunction "P$2_2") (pintype "passive"))
      (node (ref "C15") (pin "2") (pinfunction "P$2_2") (pintype "passive"))
      (node (ref "C20") (pin "2") (pinfunction "P$2_2") (pintype "passive"))
      (node (ref "C21") (pin "2") (pinfunction "P$2_2") (pintype "passive"))
      (node (ref "C22") (pin "2") (pinfunction "P$2_2") (pintype "passive"))
      (node (ref "C23") (pin "2") (pinfunction "P$2_2") (pintype "passive"))
      (node (ref "C24") (pin "2") (pinfunction "P$2_2") (pintype "passive"))
      (node (ref "C25") (pin "2") (pinfunction "P$2_2") (pintype "passive"))
      (node (ref "CP3") (pin "+") (pinfunction "+_+") (pintype "passive"))
      (node (ref "D1") (pin "A") (pinfunction "A_A") (pintype "bidirectional"))
      (node (ref "D2") (pin "A") (pinfunction "A_A") (pintype "bidirectional"))
      (node (ref "D3") (pin "A") (pinfunction "A_A") (pintype "bidirectional"))
      (node (ref "D4") (pin "A") (pinfunction "A_A") (pintype "bidirectional"))
      (node (ref "IC1") (pin "8") (pinfunction "V+_8") (pintype "power_in"))
      (node (ref "IC10") (pin "10") (pinfunction "PR_10") (pintype "bidirectional"))
      (node (ref "IC10") (pin "13") (pinfunction "VL_13") (pintype "power_in"))
      (node (ref "IC10") (pin "5") (pinfunction "VDD_5") (pintype "power_in"))
      (node (ref "IC10") (pin "6") (pinfunction "SHDN_6") (pintype "bidirectional"))
      (node (ref "IC2") (pin "8") (pinfunction "V+_8") (pintype "power_in"))
      (node (ref "IC4") (pin "10") (pinfunction "PR_10") (pintype "bidirectional"))
      (node (ref "IC4") (pin "13") (pinfunction "VL_13") (pintype "power_in"))
      (node (ref "IC4") (pin "5") (pinfunction "VDD_5") (pintype "power_in"))
      (node (ref "IC4") (pin "6") (pinfunction "SHDN_6") (pintype "bidirectional"))
      (node (ref "IC5") (pin "10") (pinfunction "PR_10") (pintype "bidirectional"))
      (node (ref "IC5") (pin "13") (pinfunction "VL_13") (pintype "power_in"))
      (node (ref "IC5") (pin "5") (pinfunction "VDD_5") (pintype "power_in"))
      (node (ref "IC5") (pin "6") (pinfunction "SHDN_6") (pintype "bidirectional"))
      (node (ref "IC6") (pin "1") (pinfunction "IN_1") (pintype "bidirectional"))
      (node (ref "IC7") (pin "8") (pinfunction "V+_8") (pintype "power_in"))
      (node (ref "IC8") (pin "10") (pinfunction "PR_10") (pintype "bidirectional"))
      (node (ref "IC8") (pin "13") (pinfunction "VL_13") (pintype "power_in"))
      (node (ref "IC8") (pin "5") (pinfunction "VDD_5") (pintype "power_in"))
      (node (ref "IC8") (pin "6") (pinfunction "SHDN_6") (pintype "bidirectional"))
      (node (ref "IC9") (pin "8") (pinfunction "V+_8") (pintype "power_in"))
      (node (ref "JP1") (pin "11") (pinfunction "11_11") (pintype "passive"))
      (node (ref "JP1") (pin "2") (pinfunction "2_2") (pintype "passive"))
      (node (ref "JP11") (pin "11") (pinfunction "11_11") (pintype "passive"))
      (node (ref "JP11") (pin "2") (pinfunction "2_2") (pintype "passive"))
      (node (ref "JP2") (pin "11") (pinfunction "11_11") (pintype "passive"))
      (node (ref "JP2") (pin "2") (pinfunction "2_2") (pintype "passive"))
      (node (ref "JP8") (pin "11") (pinfunction "11_11") (pintype "passive"))
      (node (ref "JP8") (pin "2") (pinfunction "2_2") (pintype "passive"))
      (node (ref "L1") (pin "2") (pinfunction "P$2_2") (pintype "passive"))
      (node (ref "L2") (pin "2") (pinfunction "P$2_2") (pintype "passive"))
      (node (ref "L4") (pin "1") (pinfunction "P$1_1") (pintype "passive"))
      (node (ref "R11") (pin "2") (pinfunction "P$2_2") (pintype "passive"))
      (node (ref "R12") (pin "2") (pinfunction "P$2_2") (pintype "passive"))
      (node (ref "R19") (pin "2") (pinfunction "P$2_2") (pintype "passive"))
      (node (ref "R28") (pin "P$2") (pinfunction "2_P$2") (pintype "passive"))
      (node (ref "R29") (pin "2") (pinfunction "P$2_2") (pintype "passive"))
      (node (ref "R32") (pin "2") (pinfunction "P$2_2") (pintype "passive"))
      (node (ref "R33") (pin "P$2") (pinfunction "2_P$2") (pintype "passive"))
      (node (ref "R34") (pin "2") (pinfunction "P$2_2") (pintype "passive"))
      (node (ref "R43") (pin "2") (pinfunction "P$2_2") (pintype "passive"))
      (node (ref "R44") (pin "2") (pinfunction "P$2_2") (pintype "passive"))
      (node (ref "R46") (pin "2") (pinfunction "P$2_2") (pintype "passive"))
      (node (ref "R47") (pin "2") (pinfunction "P$2_2") (pintype "passive"))
      (node (ref "R61") (pin "2") (pinfunction "P$2_2") (pintype "passive"))
      (node (ref "R62") (pin "2") (pinfunction "P$2_2") (pintype "passive"))
      (node (ref "R64") (pin "2") (pinfunction "P$2_2") (pintype "passive"))
      (node (ref "R65") (pin "2") (pinfunction "P$2_2") (pintype "passive"))
      (node (ref "R79") (pin "2") (pinfunction "P$2_2") (pintype "passive"))
      (node (ref "R8") (pin "2") (pinfunction "P$2_2") (pintype "passive"))
      (node (ref "R80") (pin "2") (pinfunction "P$2_2") (pintype "passive"))
      (node (ref "R82") (pin "2") (pinfunction "P$2_2") (pintype "passive"))
      (node (ref "R83") (pin "2") (pinfunction "P$2_2") (pintype "passive"))
      (node (ref "R9") (pin "2") (pinfunction "P$2_2") (pintype "passive"))
    )
    (net (code "109") (name "VMON1") (class "Default")
      (node (ref "JP1") (pin "7") (pinfunction "7_7") (pintype "passive"))
      (node (ref "R18") (pin "1") (pinfunction "P$1_1") (pintype "passive"))
      (node (ref "R26") (pin "P$2") (pinfunction "2_P$2") (pintype "passive"))
    )
    (net (code "110") (name "VMON1_B") (class "Default")
      (node (ref "C9") (pin "2") (pinfunction "P$2_2") (pintype "passive"))
      (node (ref "R26") (pin "P$1") (pinfunction "1_P$1") (pintype "passive"))
      (node (ref "R27") (pin "P$2") (pinfunction "2_P$2") (pintype "passive"))
      (node (ref "U$1") (pin "A10") (pinfunction "A10_A10") (pintype "bidirectional"))
    )
    (net (code "111") (name "VMON2") (class "Default")
      (node (ref "JP2") (pin "7") (pinfunction "7_7") (pintype "passive"))
      (node (ref "R24") (pin "P$2") (pinfunction "2_P$2") (pintype "passive"))
      (node (ref "R54") (pin "1") (pinfunction "P$1_1") (pintype "passive"))
    )
    (net (code "112") (name "VMON2_B") (class "Default")
      (node (ref "C6") (pin "2") (pinfunction "P$2_2") (pintype "passive"))
      (node (ref "R24") (pin "P$1") (pinfunction "1_P$1") (pintype "passive"))
      (node (ref "R25") (pin "P$2") (pinfunction "2_P$2") (pintype "passive"))
      (node (ref "U$1") (pin "22/A8") (pinfunction "22/A8/T/PWM_22/A8") (pintype "bidirectional"))
    )
    (net (code "113") (name "VMON3") (class "Default")
      (node (ref "JP8") (pin "7") (pinfunction "7_7") (pintype "passive"))
      (node (ref "R22") (pin "P$2") (pinfunction "2_P$2") (pintype "passive"))
      (node (ref "R72") (pin "1") (pinfunction "P$1_1") (pintype "passive"))
    )
    (net (code "114") (name "VMON3_B") (class "Default")
      (node (ref "C4") (pin "2") (pinfunction "P$2_2") (pintype "passive"))
      (node (ref "R22") (pin "P$1") (pinfunction "1_P$1") (pintype "passive"))
      (node (ref "R23") (pin "P$2") (pinfunction "2_P$2") (pintype "passive"))
      (node (ref "U$1") (pin "20/A6") (pinfunction "20/A6/PWM_20/A6") (pintype "bidirectional"))
    )
    (net (code "115") (name "VMON4") (class "Default")
      (node (ref "JP11") (pin "7") (pinfunction "7_7") (pintype "passive"))
      (node (ref "R20") (pin "P$2") (pinfunction "2_P$2") (pintype "passive"))
      (node (ref "R90") (pin "1") (pinfunction "P$1_1") (pintype "passive"))
    )
    (net (code "116") (name "VMON4_B") (class "Default")
      (node (ref "C3") (pin "2") (pinfunction "P$2_2") (pintype "passive"))
      (node (ref "R20") (pin "P$1") (pinfunction "1_P$1") (pintype "passive"))
      (node (ref "R21") (pin "P$2") (pinfunction "2_P$2") (pintype "passive"))
      (node (ref "U$1") (pin "18/A4") (pinfunction "18/A4/T/SDA0_18/A4") (pintype "bidirectional"))
    )
    (net (code "117") (name "VSET1") (class "Default")
      (node (ref "IC1") (pin "3") (pinfunction "+IN_3") (pintype "input"))
      (node (ref "IC1") (pin "6") (pinfunction "-IN_6") (pintype "input"))
      (node (ref "IC3") (pin "1") (pinfunction "VOUTA_1") (pintype "output"))
      (node (ref "JP1") (pin "10") (pinfunction "10_10") (pintype "passive"))
      (node (ref "TP8") (pin "P$1") (pinfunction "P$1_P$1") (pintype "bidirectional"))
    )
    (net (code "118") (name "VSET2") (class "Default")
      (node (ref "IC2") (pin "3") (pinfunction "+IN_3") (pintype "input"))
      (node (ref "IC2") (pin "6") (pinfunction "-IN_6") (pintype "input"))
      (node (ref "IC3") (pin "2") (pinfunction "VOUTB_2") (pintype "output"))
      (node (ref "JP2") (pin "10") (pinfunction "10_10") (pintype "passive"))
      (node (ref "TP14") (pin "P$1") (pinfunction "P$1_P$1") (pintype "bidirectional"))
    )
    (net (code "119") (name "VSET3") (class "Default")
      (node (ref "IC3") (pin "4") (pinfunction "VOUTC_4") (pintype "output"))
      (node (ref "IC7") (pin "3") (pinfunction "+IN_3") (pintype "input"))
      (node (ref "IC7") (pin "6") (pinfunction "-IN_6") (pintype "input"))
      (node (ref "JP8") (pin "10") (pinfunction "10_10") (pintype "passive"))
      (node (ref "TP20") (pin "P$1") (pinfunction "P$1_P$1") (pintype "bidirectional"))
    )
    (net (code "120") (name "VSET4") (class "Default")
      (node (ref "IC3") (pin "5") (pinfunction "VOUTD_5") (pintype "output"))
      (node (ref "IC9") (pin "3") (pinfunction "+IN_3") (pintype "input"))
      (node (ref "IC9") (pin "6") (pinfunction "-IN_6") (pintype "input"))
      (node (ref "JP11") (pin "10") (pinfunction "10_10") (pintype "passive"))
      (node (ref "TP26") (pin "P$1") (pinfunction "P$1_P$1") (pintype "bidirectional"))
    )
    (net (code "121") (name "VUSB") (class "Default")
      (node (ref "U$1") (pin "VUSB") (pinfunction "VUSB_VUSB") (pintype "power_in"))
    )
    (net (code "122") (name "unconnected-(IC4-SDO-Pad1)") (class "Default")
      (node (ref "IC4") (pin "1") (pinfunction "SDO_1") (pintype "bidirectional"))
    )
    (net (code "123") (name "unconnected-(IC5-SDO-Pad1)") (class "Default")
      (node (ref "IC5") (pin "1") (pinfunction "SDO_1") (pintype "bidirectional"))
    )
    (net (code "124") (name "unconnected-(IC8-SDO-Pad1)") (class "Default")
      (node (ref "IC8") (pin "1") (pinfunction "SDO_1") (pintype "bidirectional"))
    )
    (net (code "125") (name "unconnected-(IC10-SDO-Pad1)") (class "Default")
      (node (ref "IC10") (pin "1") (pinfunction "SDO_1") (pintype "bidirectional"))
    )
    (net (code "126") (name "unconnected-(S1-1-PadP$1)") (class "Default")
      (node (ref "S1") (pin "P$1") (pinfunction "1_P$1") (pintype "bidirectional"))
    )
    (net (code "127") (name "unconnected-(S2-1-PadP$1)") (class "Default")
      (node (ref "S2") (pin "P$1") (pinfunction "1_P$1") (pintype "bidirectional"))
    )
    (net (code "128") (name "unconnected-(S3-1-PadP$1)") (class "Default")
      (node (ref "S3") (pin "P$1") (pinfunction "1_P$1") (pintype "bidirectional"))
    )
    (net (code "129") (name "unconnected-(S4-1-PadP$1)") (class "Default")
      (node (ref "S4") (pin "P$1") (pinfunction "1_P$1") (pintype "bidirectional"))
    )
    (net (code "130") (name "unconnected-(U$1-A14{slash}DAC-PadA14)") (class "Default")
      (node (ref "U$1") (pin "A14") (pinfunction "A14/DAC_A14") (pintype "bidirectional"))
    )
    (net (code "131") (name "unconnected-(U$1-PadPGM)") (class "Default")
      (node (ref "U$1") (pin "PGM") (pinfunction "PGM_PGM") (pintype "bidirectional"))
    )
  )
)
